# TP-34ren.net
KiCad netlist of a schematic drawn in EAGLE
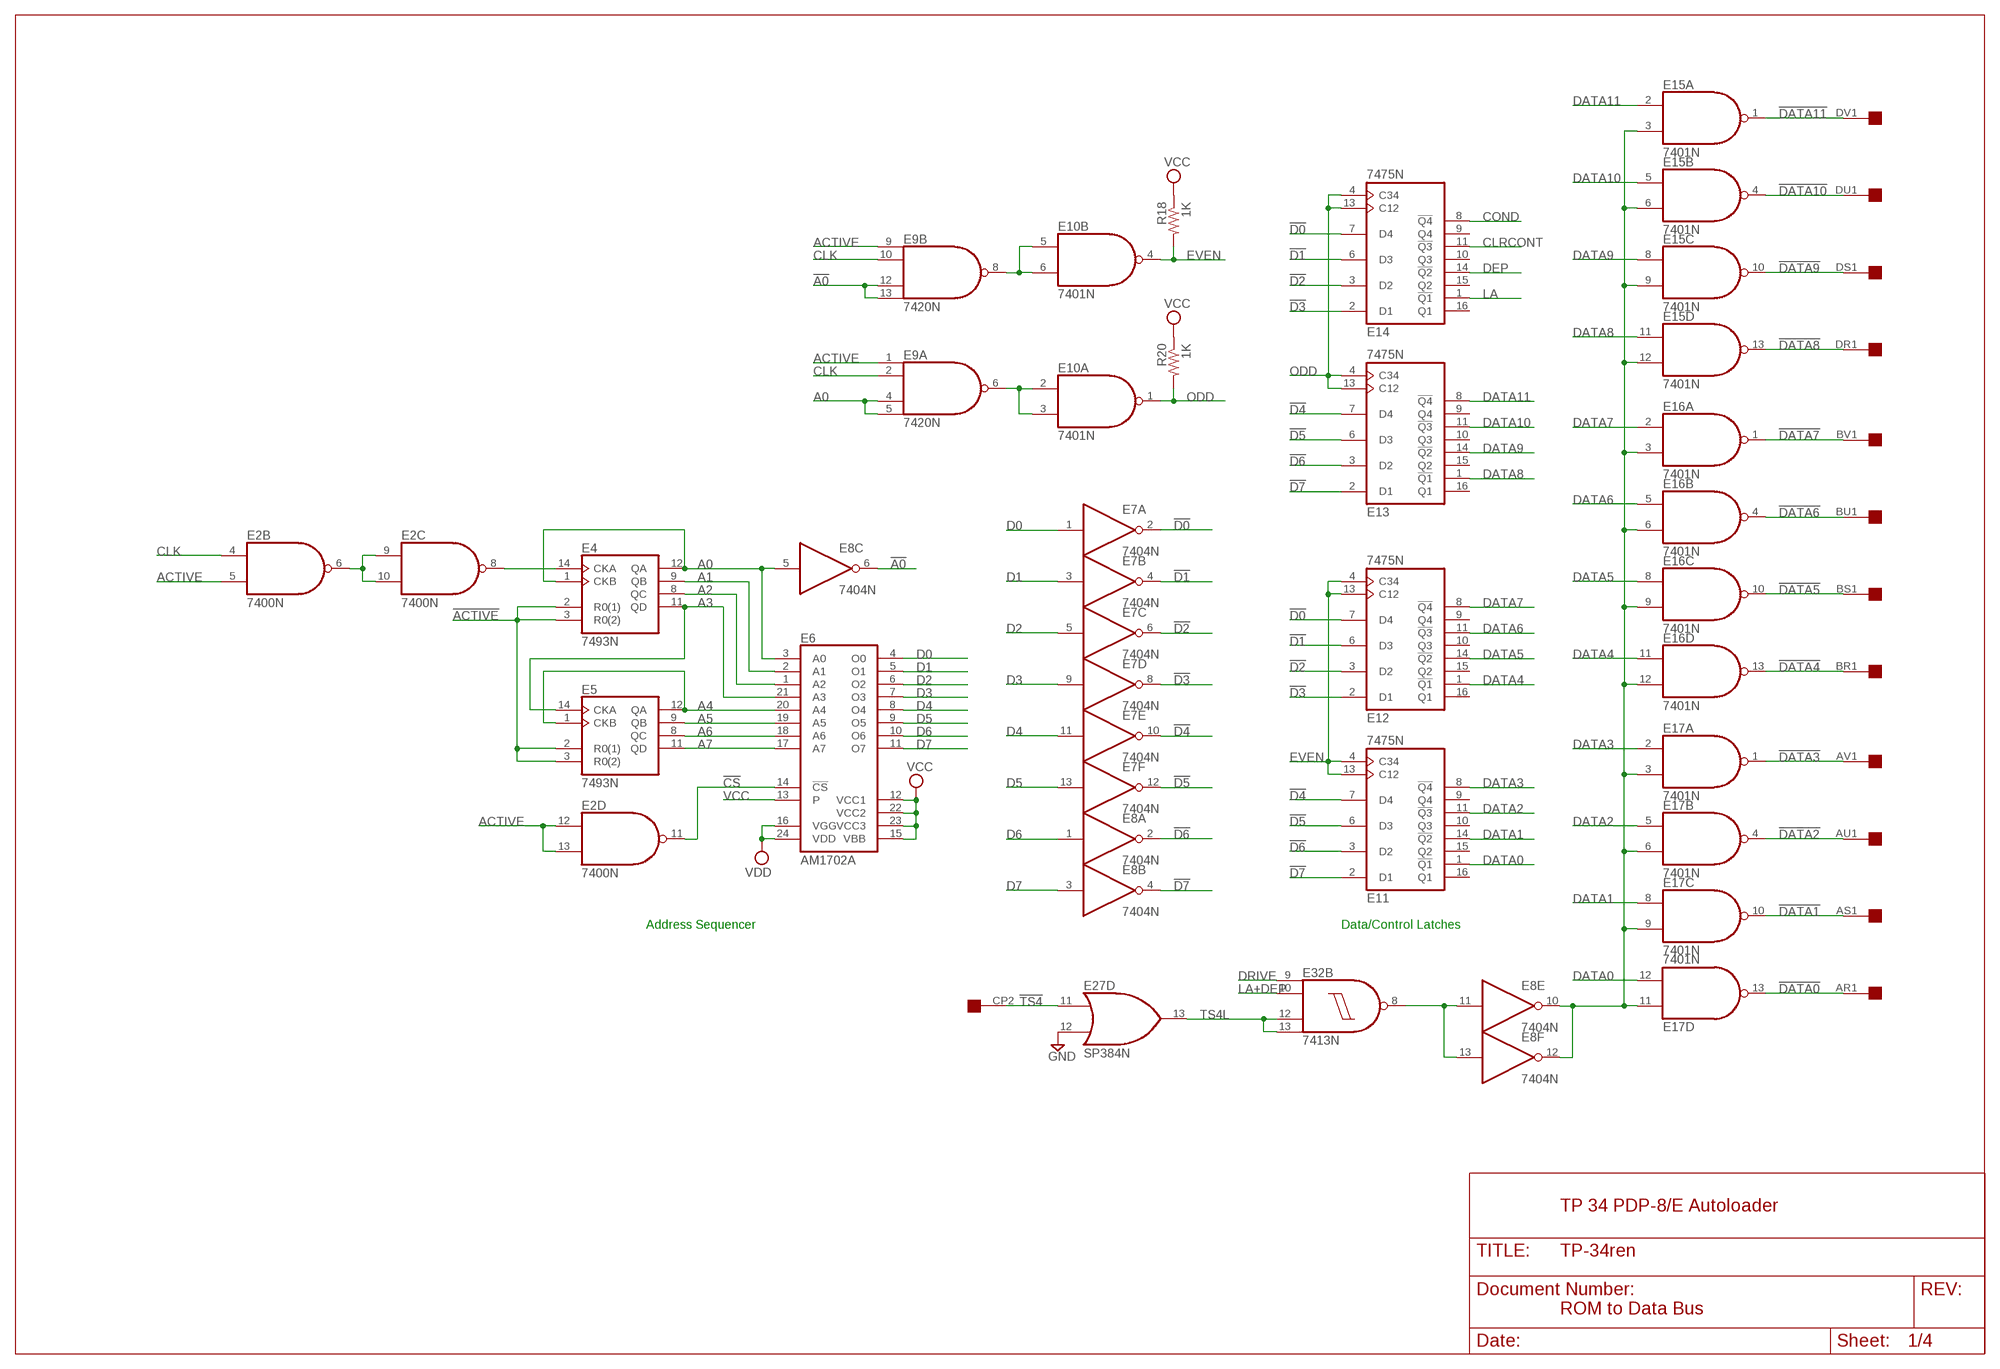
[diagram p0: schematic, sheet 1]
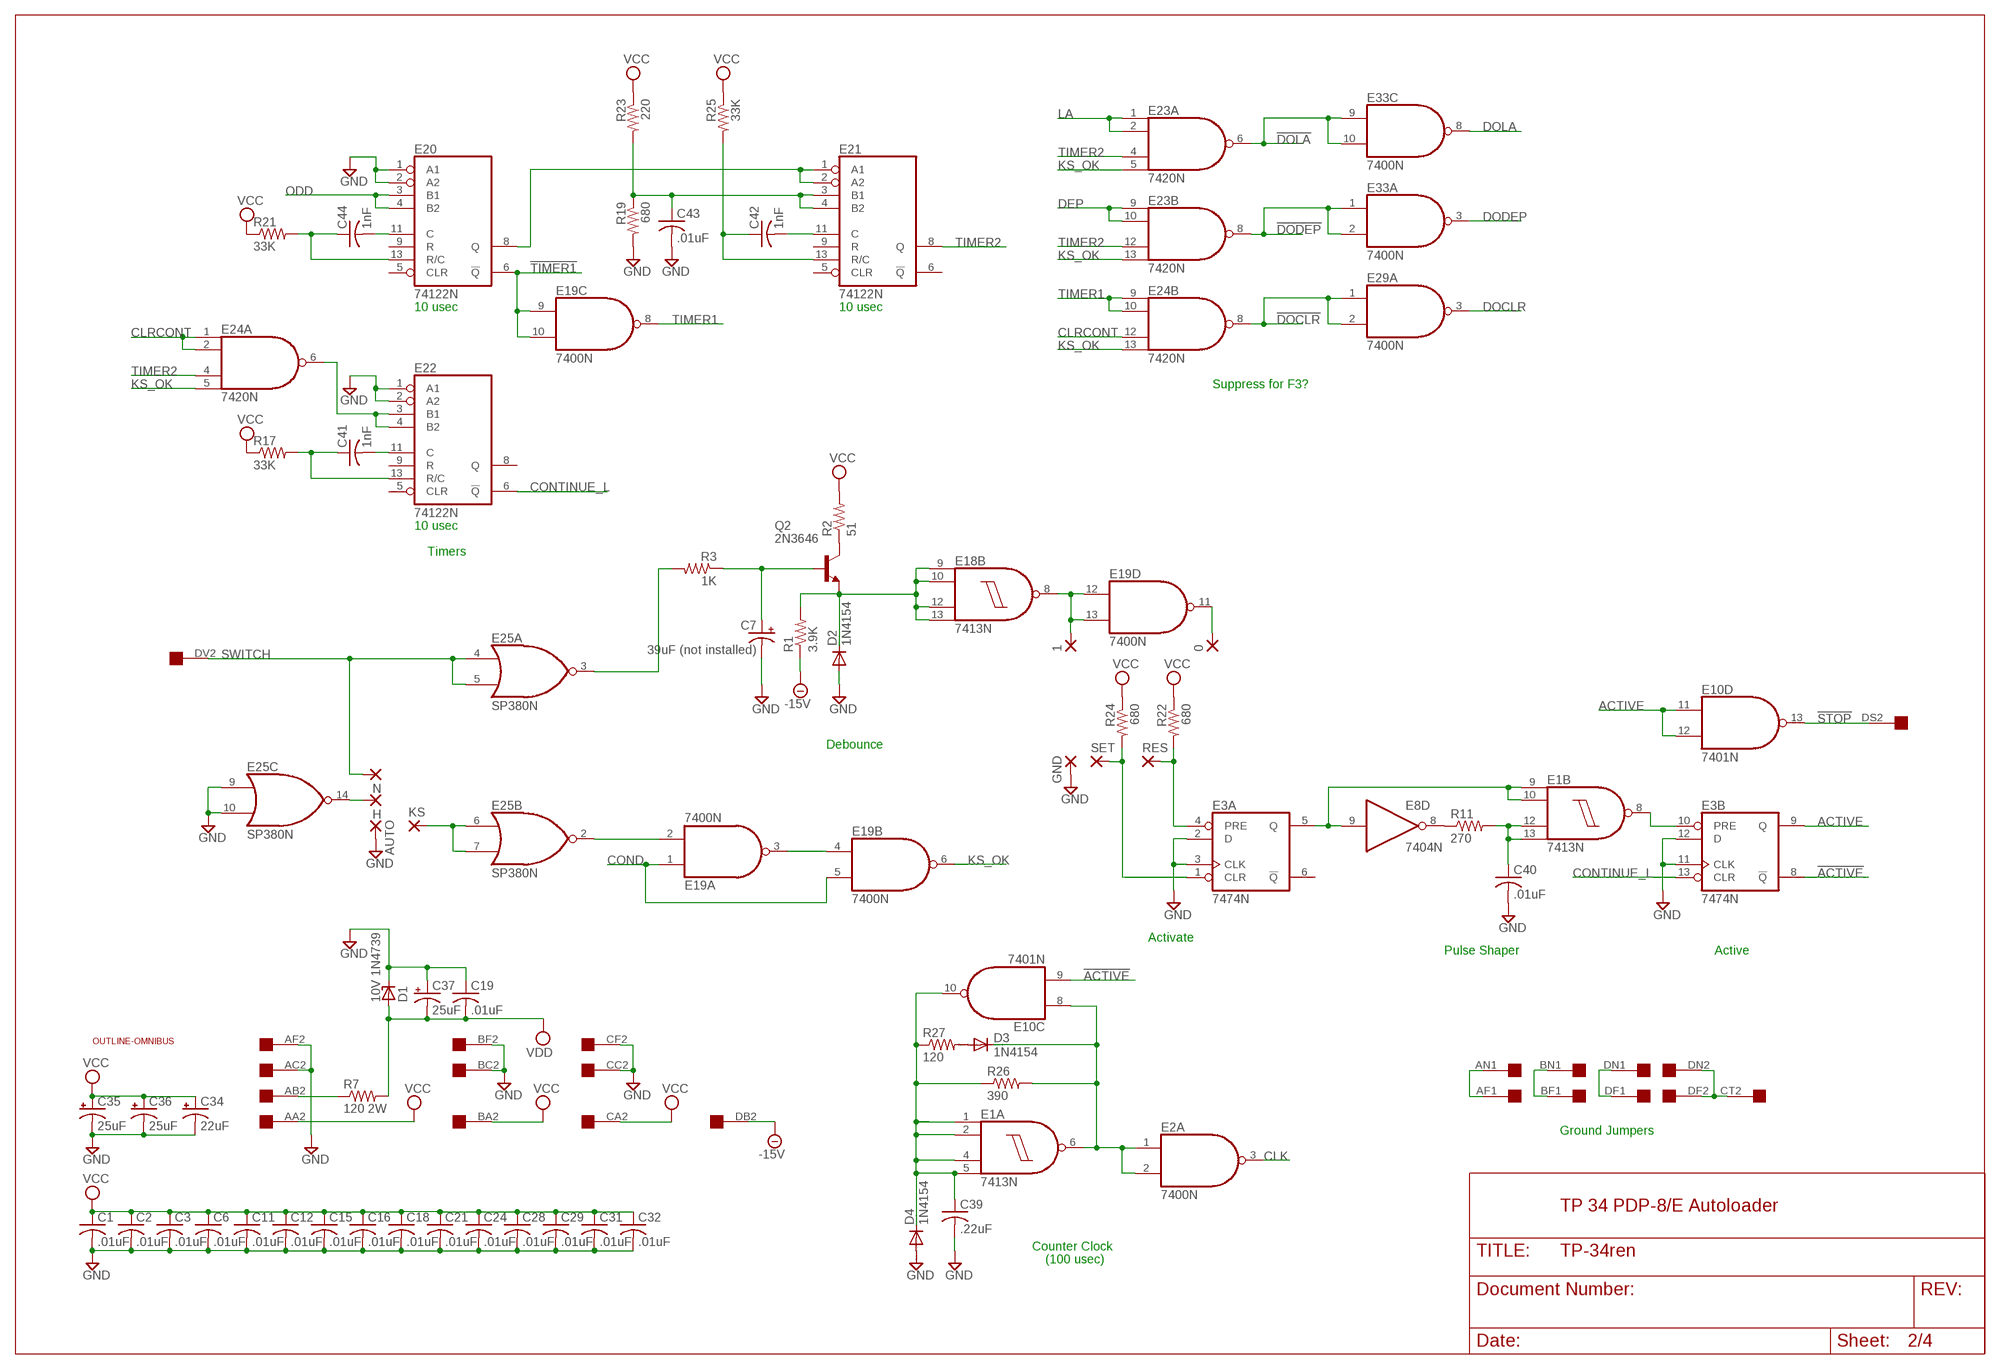
[diagram p1: schematic, sheet 2]
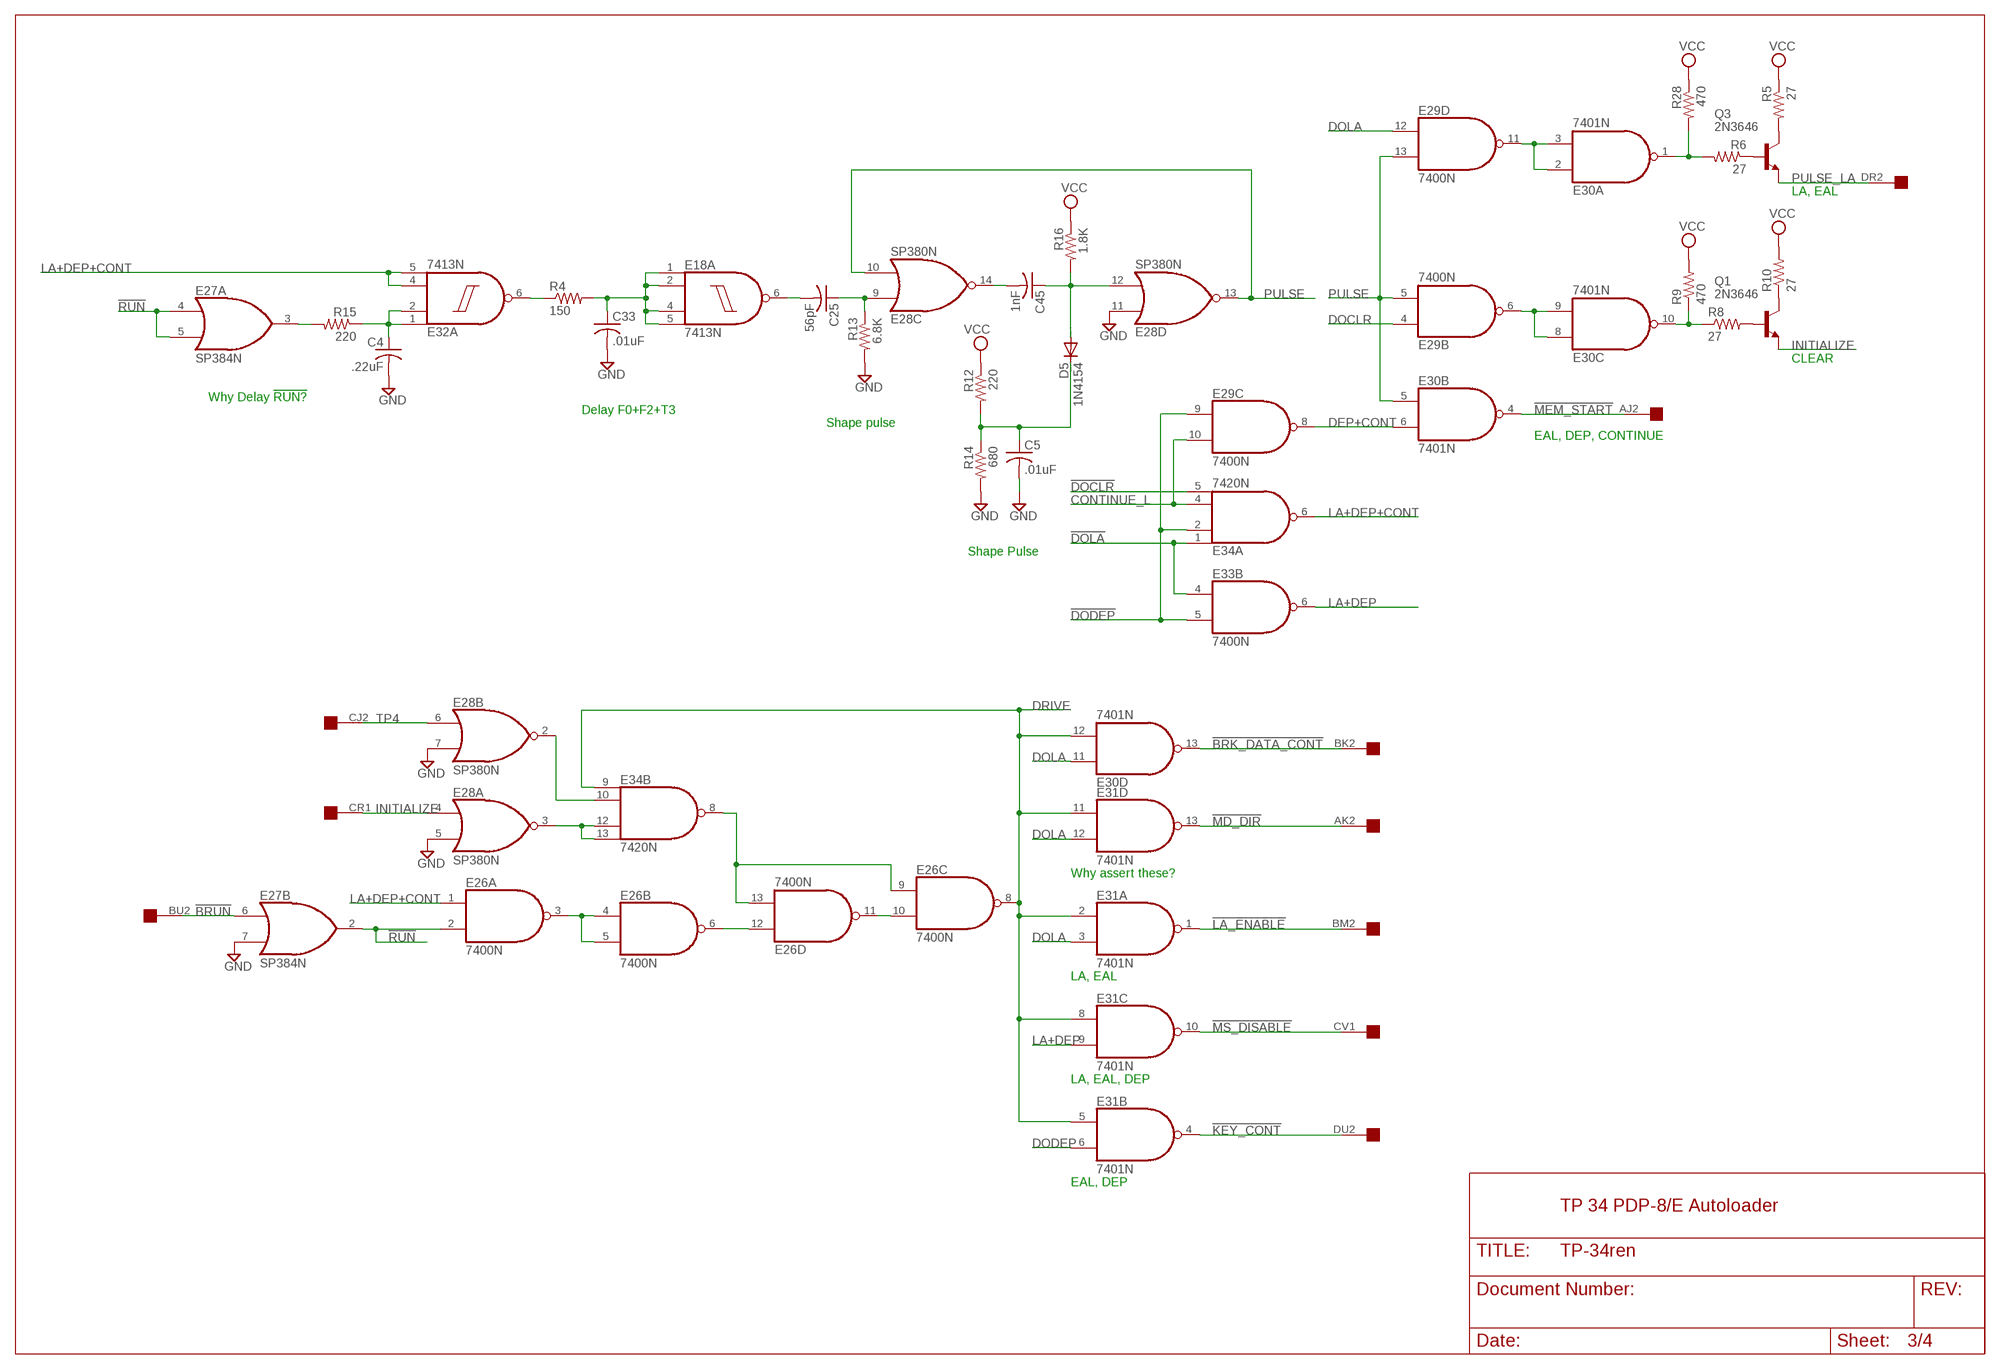
[diagram p2: schematic, sheet 3]
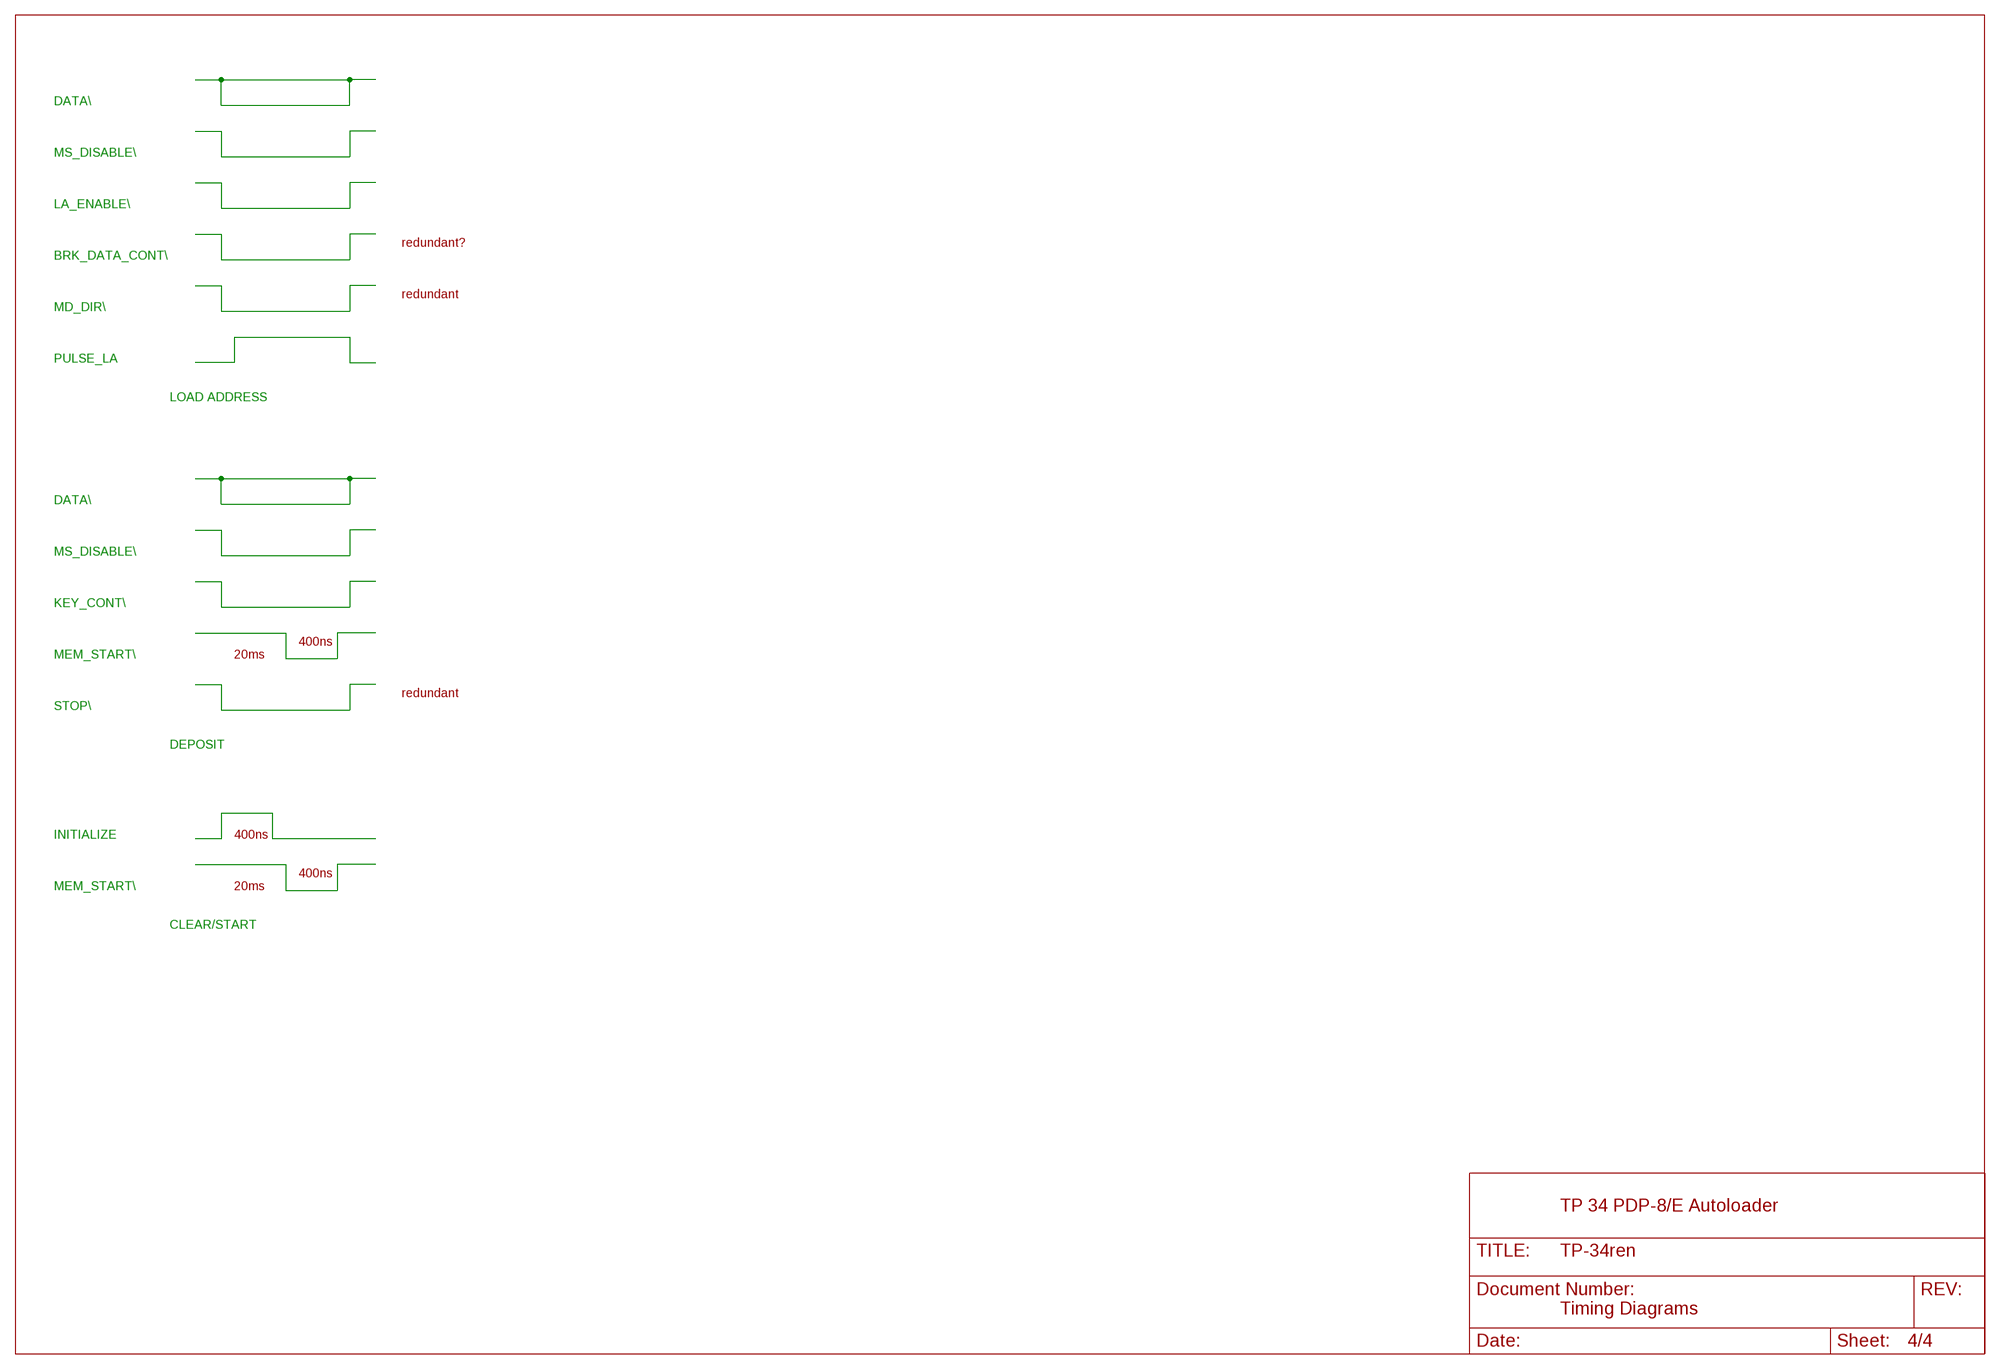
[diagram p3: schematic, sheet 4]

(export (version "E")
  (design (tool "Eeschema 10.0.6"))
  (components
    (comp (ref "0")
      (value "1,6/0,8")
      (footprint "eagle-import:1,6_0,8")
      (libsource (lib "eagle-import") (part "1,6/0,8"))
    )
    (comp (ref "1")
      (value "1,6/0,8")
      (footprint "eagle-import:1,6_0,8")
      (libsource (lib "eagle-import") (part "1,6/0,8"))
    )
    (comp (ref "AUTO")
      (value "1,6/0,8")
      (footprint "eagle-import:1,6_0,8")
      (libsource (lib "eagle-import") (part "1,6/0,8"))
    )
    (comp (ref "C1")
      (value ".01uF")
      (footprint "eagle-import:C075-032X103")
      (libsource (lib "eagle-import") (part "C-US075-032X103"))
    )
    (comp (ref "C2")
      (value ".01uF")
      (footprint "eagle-import:C075-032X103")
      (libsource (lib "eagle-import") (part "C-US075-032X103"))
    )
    (comp (ref "C3")
      (value ".01uF")
      (footprint "eagle-import:C075-032X103")
      (libsource (lib "eagle-import") (part "C-US075-032X103"))
    )
    (comp (ref "C6")
      (value ".01uF")
      (footprint "eagle-import:C075-032X103")
      (libsource (lib "eagle-import") (part "C-US075-032X103"))
    )
    (comp (ref "C7")
      (value "39uF (not installed)")
      (footprint "eagle-import:E15-5")
      (libsource (lib "eagle-import") (part "CPOL-USE15-5AXIAL"))
    )
    (comp (ref "C11")
      (value ".01uF")
      (footprint "eagle-import:C075-032X103")
      (libsource (lib "eagle-import") (part "C-US075-032X103"))
    )
    (comp (ref "C12")
      (value ".01uF")
      (footprint "eagle-import:C075-032X103")
      (libsource (lib "eagle-import") (part "C-US075-032X103"))
    )
    (comp (ref "C15")
      (value ".01uF")
      (footprint "eagle-import:C075-032X103")
      (libsource (lib "eagle-import") (part "C-US075-032X103"))
    )
    (comp (ref "C16")
      (value ".01uF")
      (footprint "eagle-import:C075-032X103")
      (libsource (lib "eagle-import") (part "C-US075-032X103"))
    )
    (comp (ref "C18")
      (value ".01uF")
      (footprint "eagle-import:C075-032X103")
      (libsource (lib "eagle-import") (part "C-US075-032X103"))
    )
    (comp (ref "C19")
      (value ".01uF")
      (footprint "eagle-import:C075-032X103")
      (libsource (lib "eagle-import") (part "C-US075-032X103"))
    )
    (comp (ref "C21")
      (value ".01uF")
      (footprint "eagle-import:C075-032X103")
      (libsource (lib "eagle-import") (part "C-US075-032X103"))
    )
    (comp (ref "C24")
      (value ".01uF")
      (footprint "eagle-import:C075-032X103")
      (libsource (lib "eagle-import") (part "C-US075-032X103"))
    )
    (comp (ref "C28")
      (value ".01uF")
      (footprint "eagle-import:C075-032X103")
      (libsource (lib "eagle-import") (part "C-US075-032X103"))
    )
    (comp (ref "C29")
      (value ".01uF")
      (footprint "eagle-import:C075-032X103")
      (libsource (lib "eagle-import") (part "C-US075-032X103"))
    )
    (comp (ref "C31")
      (value ".01uF")
      (footprint "eagle-import:C075-032X103")
      (libsource (lib "eagle-import") (part "C-US075-032X103"))
    )
    (comp (ref "C32")
      (value ".01uF")
      (footprint "eagle-import:C075-032X103")
      (libsource (lib "eagle-import") (part "C-US075-032X103"))
    )
    (comp (ref "C34")
      (value "22uF")
      (footprint "eagle-import:E12-8")
      (libsource (lib "eagle-import") (part "CPOL-USE20-8AXIAL"))
    )
    (comp (ref "C35")
      (value "25uF")
      (footprint "eagle-import:E15-5")
      (libsource (lib "eagle-import") (part "CPOL-USE15-5AXIAL"))
    )
    (comp (ref "C36")
      (value "25uF")
      (footprint "eagle-import:E15-5")
      (libsource (lib "eagle-import") (part "CPOL-USE15-5AXIAL"))
    )
    (comp (ref "C37")
      (value "25uF")
      (footprint "eagle-import:E15-5")
      (libsource (lib "eagle-import") (part "CPOL-USE15-5AXIAL"))
    )
    (comp (ref "C39")
      (value ".22uF")
      (footprint "eagle-import:C075-032X103")
      (libsource (lib "eagle-import") (part "C-US075-032X103"))
    )
    (comp (ref "C40")
      (value ".01uF")
      (footprint "eagle-import:C075-032X103")
      (libsource (lib "eagle-import") (part "C-US075-032X103"))
    )
    (comp (ref "C41")
      (value "1nF")
      (footprint "eagle-import:C075-032X103")
      (libsource (lib "eagle-import") (part "C-US075-032X103"))
    )
    (comp (ref "C42")
      (value "1nF")
      (footprint "eagle-import:C075-032X103")
      (libsource (lib "eagle-import") (part "C-US075-032X103"))
    )
    (comp (ref "C43")
      (value ".01uF")
      (footprint "eagle-import:C075-032X103")
      (libsource (lib "eagle-import") (part "C-US075-032X103"))
    )
    (comp (ref "C44")
      (value "1nF")
      (footprint "eagle-import:C075-032X103")
      (libsource (lib "eagle-import") (part "C-US075-032X103"))
    )
    (comp (ref "D1")
      (value "10V 1N4739")
      (footprint "eagle-import:C1702-15")
      (libsource (lib "eagle-import") (part "ZENER-DIODEC1702-15"))
    )
    (comp (ref "D2")
      (value "1N4154")
      (footprint "eagle-import:DO35-10")
      (libsource (lib "eagle-import") (part "1N4148DO35-10"))
    )
    (comp (ref "D3")
      (value "1N4154")
      (footprint "eagle-import:DO35-10")
      (libsource (lib "eagle-import") (part "1N4148DO35-10"))
    )
    (comp (ref "D4")
      (value "1N4154")
      (footprint "eagle-import:DO35-10")
      (libsource (lib "eagle-import") (part "1N4148DO35-10"))
    )
    (comp (ref "E1")
      (value "7413N")
      (footprint "eagle-import:DIL14")
      (libsource (lib "eagle-import") (part "7413N"))
    )
    (comp (ref "E2")
      (value "7400N")
      (footprint "eagle-import:DIL14")
      (libsource (lib "eagle-import") (part "7400N"))
    )
    (comp (ref "E3")
      (value "7474N")
      (footprint "eagle-import:DIL14")
      (libsource (lib "eagle-import") (part "7474NS"))
    )
    (comp (ref "E8")
      (value "7404N")
      (footprint "eagle-import:DIL14")
      (libsource (lib "eagle-import") (part "7404N"))
    )
    (comp (ref "E10")
      (value "7401N")
      (footprint "eagle-import:DIL14")
      (libsource (lib "eagle-import") (part "7401NLS"))
    )
    (comp (ref "E18")
      (value "7413N")
      (footprint "eagle-import:DIL14")
      (libsource (lib "eagle-import") (part "7413N"))
    )
    (comp (ref "E19")
      (value "7400N")
      (footprint "eagle-import:DIL14")
      (libsource (lib "eagle-import") (part "7400N"))
    )
    (comp (ref "E20")
      (value "74122N")
      (footprint "eagle-import:DIL14")
      (libsource (lib "eagle-import") (part "74122NLS"))
    )
    (comp (ref "E21")
      (value "74122N")
      (footprint "eagle-import:DIL14")
      (libsource (lib "eagle-import") (part "74122NLS"))
    )
    (comp (ref "E22")
      (value "74122N")
      (footprint "eagle-import:DIL14")
      (libsource (lib "eagle-import") (part "74122NLS"))
    )
    (comp (ref "E23")
      (value "7420N")
      (footprint "eagle-import:DIL14")
      (libsource (lib "eagle-import") (part "7420NS"))
    )
    (comp (ref "E24")
      (value "7420N")
      (footprint "eagle-import:DIL14")
      (libsource (lib "eagle-import") (part "7420NS"))
    )
    (comp (ref "E25")
      (value "SP380N")
      (footprint "eagle-import:DIL14")
      (libsource (lib "eagle-import") (part "SP380N"))
    )
    (comp (ref "E29")
      (value "7400N")
      (footprint "eagle-import:DIL14")
      (libsource (lib "eagle-import") (part "7400N"))
    )
    (comp (ref "E33")
      (value "7400N")
      (footprint "eagle-import:DIL14")
      (libsource (lib "eagle-import") (part "7400N"))
    )
    (comp (ref "GND")
      (value "1,6/0,8")
      (footprint "eagle-import:1,6_0,8")
      (libsource (lib "eagle-import") (part "1,6/0,8"))
    )
    (comp (ref "H")
      (value "1,6/0,8")
      (footprint "eagle-import:1,6_0,8")
      (libsource (lib "eagle-import") (part "1,6/0,8"))
    )
    (comp (ref "KS")
      (value "1,6/0,8")
      (footprint "eagle-import:1,6_0,8")
      (libsource (lib "eagle-import") (part "1,6/0,8"))
    )
    (comp (ref "N")
      (value "1,6/0,8")
      (footprint "eagle-import:1,6_0,8")
      (libsource (lib "eagle-import") (part "1,6/0,8"))
    )
    (comp (ref "Q2")
      (value "2N3646")
      (footprint "eagle-import:TO5")
      (libsource (lib "eagle-import") (part "2N2102"))
    )
    (comp (ref "R1")
      (value "3.9K")
      (footprint "eagle-import:0207_10")
      (libsource (lib "eagle-import") (part "R-US_0207/10"))
    )
    (comp (ref "R2")
      (value "51")
      (footprint "eagle-import:0207_10")
      (libsource (lib "eagle-import") (part "R-US_0207/10"))
    )
    (comp (ref "R3")
      (value "1K")
      (footprint "eagle-import:0207_10")
      (libsource (lib "eagle-import") (part "R-US_0207/10"))
    )
    (comp (ref "R7")
      (value "120 2W")
      (footprint "eagle-import:0414_15")
      (libsource (lib "eagle-import") (part "R-US_0414/15"))
    )
    (comp (ref "R11")
      (value "270")
      (footprint "eagle-import:0207_12")
      (libsource (lib "eagle-import") (part "R-US_0207/12"))
    )
    (comp (ref "R17")
      (value "33K")
      (footprint "eagle-import:0207_10")
      (libsource (lib "eagle-import") (part "R-US_0207/10"))
    )
    (comp (ref "R19")
      (value "680")
      (footprint "eagle-import:0207_10")
      (libsource (lib "eagle-import") (part "R-US_0207/10"))
    )
    (comp (ref "R21")
      (value "33K")
      (footprint "eagle-import:0207_10")
      (libsource (lib "eagle-import") (part "R-US_0207/10"))
    )
    (comp (ref "R22")
      (value "680")
      (footprint "eagle-import:0207_10")
      (libsource (lib "eagle-import") (part "R-US_0207/10"))
    )
    (comp (ref "R23")
      (value "220")
      (footprint "eagle-import:0207_10")
      (libsource (lib "eagle-import") (part "R-US_0207/10"))
    )
    (comp (ref "R24")
      (value "680")
      (footprint "eagle-import:0207_10")
      (libsource (lib "eagle-import") (part "R-US_0207/10"))
    )
    (comp (ref "R25")
      (value "33K")
      (footprint "eagle-import:0207_10")
      (libsource (lib "eagle-import") (part "R-US_0207/10"))
    )
    (comp (ref "R26")
      (value "390")
      (footprint "eagle-import:0207_10")
      (libsource (lib "eagle-import") (part "R-US_0207/10"))
    )
    (comp (ref "R27")
      (value "120")
      (footprint "eagle-import:0207_10")
      (libsource (lib "eagle-import") (part "R-US_0207/10"))
    )
    (comp (ref "RES")
      (value "1,6/0,8")
      (footprint "eagle-import:1,6_0,8")
      (libsource (lib "eagle-import") (part "1,6/0,8"))
    )
    (comp (ref "SET")
      (value "1,6/0,8")
      (footprint "eagle-import:1,6_0,8")
      (libsource (lib "eagle-import") (part "1,6/0,8"))
    )
    (comp (ref "U$1")
      (value "OUTLINE-OMNIBUS")
      (footprint "eagle-import:OMNIBUS")
      (libsource (lib "eagle-import") (part "OUTLINE-OMNIBUS"))
    )
    (comp (ref "U$2")
      (value "QUAD")
      (footprint "eagle-import:EDGE-CON8")
      (libsource (lib "eagle-import") (part "QUAD"))
    )
    (comp (ref "E4")
      (value "7493N")
      (footprint "eagle-import:DIL14")
      (libsource (lib "eagle-import") (part "7493NLS"))
    )
    (comp (ref "E5")
      (value "7493N")
      (footprint "eagle-import:DIL14")
      (libsource (lib "eagle-import") (part "7493NLS"))
    )
    (comp (ref "E6")
      (value "AM1702A")
      (footprint "eagle-import:DIL24")
      (libsource (lib "eagle-import") (part "AM1702"))
    )
    (comp (ref "E7")
      (value "7404N")
      (footprint "eagle-import:DIL14")
      (libsource (lib "eagle-import") (part "7404N"))
    )
    (comp (ref "E9")
      (value "7420N")
      (footprint "eagle-import:DIL14")
      (libsource (lib "eagle-import") (part "7420NS"))
    )
    (comp (ref "E11")
      (value "7475N")
      (footprint "eagle-import:DIL16")
      (libsource (lib "eagle-import") (part "7475N"))
    )
    (comp (ref "E12")
      (value "7475N")
      (footprint "eagle-import:DIL16")
      (libsource (lib "eagle-import") (part "7475N"))
    )
    (comp (ref "E13")
      (value "7475N")
      (footprint "eagle-import:DIL16")
      (libsource (lib "eagle-import") (part "7475N"))
    )
    (comp (ref "E14")
      (value "7475N")
      (footprint "eagle-import:DIL16")
      (libsource (lib "eagle-import") (part "7475N"))
    )
    (comp (ref "E15")
      (value "7401N")
      (footprint "eagle-import:DIL14")
      (libsource (lib "eagle-import") (part "7401NLS"))
    )
    (comp (ref "E16")
      (value "7401N")
      (footprint "eagle-import:DIL14")
      (libsource (lib "eagle-import") (part "7401NLS"))
    )
    (comp (ref "E17")
      (value "7401N")
      (footprint "eagle-import:DIL14")
      (libsource (lib "eagle-import") (part "7401NLS"))
    )
    (comp (ref "E27")
      (value "SP384N")
      (footprint "eagle-import:DIL14")
      (libsource (lib "eagle-import") (part "SP384N"))
    )
    (comp (ref "E32")
      (value "7413N")
      (footprint "eagle-import:DIL14")
      (libsource (lib "eagle-import") (part "7413N"))
    )
    (comp (ref "R18")
      (value "1K")
      (footprint "eagle-import:0207_10")
      (libsource (lib "eagle-import") (part "R-US_0207/10"))
    )
    (comp (ref "R20")
      (value "1K")
      (footprint "eagle-import:0207_10")
      (libsource (lib "eagle-import") (part "R-US_0207/10"))
    )
    (comp (ref "C4")
      (value ".22uF")
      (footprint "eagle-import:C075-032X103")
      (libsource (lib "eagle-import") (part "C-US075-032X103"))
    )
    (comp (ref "C5")
      (value ".01uF")
      (footprint "eagle-import:C075-032X103")
      (libsource (lib "eagle-import") (part "C-US075-032X103"))
    )
    (comp (ref "C25")
      (value "56pF")
      (footprint "eagle-import:C102-043X133")
      (libsource (lib "eagle-import") (part "C-US102-043X133"))
    )
    (comp (ref "C33")
      (value ".01uF")
      (footprint "eagle-import:C075-032X103")
      (libsource (lib "eagle-import") (part "C-US075-032X103"))
    )
    (comp (ref "C45")
      (value "1nF")
      (footprint "eagle-import:C050-035X075")
      (libsource (lib "eagle-import") (part "C-US050-035X075"))
    )
    (comp (ref "D5")
      (value "1N4154")
      (footprint "eagle-import:DO35-10")
      (libsource (lib "eagle-import") (part "1N4148DO35-10"))
    )
    (comp (ref "E26")
      (value "7400N")
      (footprint "eagle-import:DIL14")
      (libsource (lib "eagle-import") (part "7400N"))
    )
    (comp (ref "E28")
      (value "SP380N")
      (footprint "eagle-import:DIL14")
      (libsource (lib "eagle-import") (part "SP380N"))
    )
    (comp (ref "E30")
      (value "7401N")
      (footprint "eagle-import:DIL14")
      (libsource (lib "eagle-import") (part "7401NLS"))
    )
    (comp (ref "E31")
      (value "7401N")
      (footprint "eagle-import:DIL14")
      (libsource (lib "eagle-import") (part "7401NLS"))
    )
    (comp (ref "E34")
      (value "7420N")
      (footprint "eagle-import:DIL14")
      (libsource (lib "eagle-import") (part "7420NS"))
    )
    (comp (ref "Q1")
      (value "2N3646")
      (footprint "eagle-import:TO5")
      (libsource (lib "eagle-import") (part "2N2102"))
    )
    (comp (ref "Q3")
      (value "2N3646")
      (footprint "eagle-import:TO5")
      (libsource (lib "eagle-import") (part "2N2102"))
    )
    (comp (ref "R4")
      (value "150")
      (footprint "eagle-import:0207_10")
      (libsource (lib "eagle-import") (part "R-US_0207/10"))
    )
    (comp (ref "R5")
      (value "27")
      (footprint "eagle-import:0207_10")
      (libsource (lib "eagle-import") (part "R-US_0207/10"))
    )
    (comp (ref "R6")
      (value "27")
      (footprint "eagle-import:0207_10")
      (libsource (lib "eagle-import") (part "R-US_0207/10"))
    )
    (comp (ref "R8")
      (value "27")
      (footprint "eagle-import:0207_10")
      (libsource (lib "eagle-import") (part "R-US_0207/10"))
    )
    (comp (ref "R9")
      (value "470")
      (footprint "eagle-import:0207_10")
      (libsource (lib "eagle-import") (part "R-US_0207/10"))
    )
    (comp (ref "R10")
      (value "27")
      (footprint "eagle-import:0207_10")
      (libsource (lib "eagle-import") (part "R-US_0207/10"))
    )
    (comp (ref "R12")
      (value "220")
      (footprint "eagle-import:0207_10")
      (libsource (lib "eagle-import") (part "R-US_0207/10"))
    )
    (comp (ref "R13")
      (value "6.8K")
      (footprint "eagle-import:0207_10")
      (libsource (lib "eagle-import") (part "R-US_0207/10"))
    )
    (comp (ref "R14")
      (value "680")
      (footprint "eagle-import:0207_10")
      (libsource (lib "eagle-import") (part "R-US_0207/10"))
    )
    (comp (ref "R15")
      (value "220")
      (footprint "eagle-import:0207_15")
      (libsource (lib "eagle-import") (part "R-US_0207/15"))
    )
    (comp (ref "R16")
      (value "1.8K")
      (footprint "eagle-import:0207_10")
      (libsource (lib "eagle-import") (part "R-US_0207/10"))
    )
    (comp (ref "R28")
      (value "470")
      (footprint "eagle-import:0207_10")
      (libsource (lib "eagle-import") (part "R-US_0207/10"))
    )
  )
  (nets
    (net (code "1") (name "-15V") (class "Default")
      (node (ref "R1") (pin "1") (pinfunction "1_1") (pintype "passive"))
      (node (ref "U$2") (pin "DB2") (pinfunction "1_DB2") (pintype "bidirectional"))
    )
    (net (code "2") (name "A0") (class "Default")
      (node (ref "E4") (pin "1") (pinfunction "CKB_1") (pintype "input"))
      (node (ref "E4") (pin "12") (pinfunction "QA_12") (pintype "output"))
      (node (ref "E6") (pin "3") (pinfunction "A0_3") (pintype "input"))
      (node (ref "E8") (pin "5") (pinfunction "I_5") (pintype "input"))
      (node (ref "E9") (pin "4") (pinfunction "I2_4") (pintype "input"))
      (node (ref "E9") (pin "5") (pinfunction "I3_5") (pintype "input"))
    )
    (net (code "3") (name "A1") (class "Default")
      (node (ref "E4") (pin "9") (pinfunction "QB_9") (pintype "output"))
      (node (ref "E6") (pin "2") (pinfunction "A1_2") (pintype "input"))
    )
    (net (code "4") (name "A2") (class "Default")
      (node (ref "E4") (pin "8") (pinfunction "QC_8") (pintype "output"))
      (node (ref "E6") (pin "1") (pinfunction "A2_1") (pintype "input"))
    )
    (net (code "5") (name "A3") (class "Default")
      (node (ref "E4") (pin "11") (pinfunction "QD_11") (pintype "output"))
      (node (ref "E5") (pin "14") (pinfunction "CKA_14") (pintype "input"))
      (node (ref "E6") (pin "21") (pinfunction "A3_21") (pintype "input"))
    )
    (net (code "6") (name "A4") (class "Default")
      (node (ref "E5") (pin "1") (pinfunction "CKB_1") (pintype "input"))
      (node (ref "E5") (pin "12") (pinfunction "QA_12") (pintype "output"))
      (node (ref "E6") (pin "20") (pinfunction "A4_20") (pintype "input"))
    )
    (net (code "7") (name "A5") (class "Default")
      (node (ref "E5") (pin "9") (pinfunction "QB_9") (pintype "output"))
      (node (ref "E6") (pin "19") (pinfunction "A5_19") (pintype "input"))
    )
    (net (code "8") (name "A6") (class "Default")
      (node (ref "E5") (pin "8") (pinfunction "QC_8") (pintype "output"))
      (node (ref "E6") (pin "18") (pinfunction "A6_18") (pintype "input"))
    )
    (net (code "9") (name "A7") (class "Default")
      (node (ref "E5") (pin "11") (pinfunction "QD_11") (pintype "output"))
      (node (ref "E6") (pin "17") (pinfunction "A7_17") (pintype "input"))
    )
    (net (code "10") (name "ACTIVE") (class "Default")
      (node (ref "E10") (pin "11") (pinfunction "I0_11") (pintype "input"))
      (node (ref "E10") (pin "12") (pinfunction "I1_12") (pintype "input"))
      (node (ref "E2") (pin "12") (pinfunction "I0_12") (pintype "input"))
      (node (ref "E2") (pin "13") (pinfunction "I1_13") (pintype "input"))
      (node (ref "E2") (pin "5") (pinfunction "I1_5") (pintype "input"))
      (node (ref "E3") (pin "9") (pinfunction "Q_9") (pintype "output"))
      (node (ref "E9") (pin "1") (pinfunction "I0_1") (pintype "input"))
      (node (ref "E9") (pin "9") (pinfunction "I0_9") (pintype "input"))
    )
    (net (code "11") (name "CLK") (class "Default")
      (node (ref "E2") (pin "3") (pinfunction "O_3") (pintype "output"))
      (node (ref "E2") (pin "4") (pinfunction "I0_4") (pintype "input"))
      (node (ref "E9") (pin "10") (pinfunction "I1_10") (pintype "input"))
      (node (ref "E9") (pin "2") (pinfunction "I1_2") (pintype "input"))
    )
    (net (code "12") (name "CLRCONT") (class "Default")
      (node (ref "E14") (pin "11") (pinfunction "~{Q3}_11") (pintype "output"))
      (node (ref "E24") (pin "1") (pinfunction "I0_1") (pintype "input"))
      (node (ref "E24") (pin "12") (pinfunction "I2_12") (pintype "input"))
      (node (ref "E24") (pin "2") (pinfunction "I1_2") (pintype "input"))
    )
    (net (code "13") (name "COND") (class "Default")
      (node (ref "E14") (pin "8") (pinfunction "~{Q4}_8") (pintype "output"))
      (node (ref "E19") (pin "1") (pinfunction "I0_1") (pintype "input"))
      (node (ref "E19") (pin "5") (pinfunction "I1_5") (pintype "input"))
    )
    (net (code "14") (name "CONTINUE_L") (class "Default")
      (node (ref "E22") (pin "6") (pinfunction "~{Q}_6") (pintype "output"))
      (node (ref "E29") (pin "10") (pinfunction "I1_10") (pintype "input"))
      (node (ref "E3") (pin "13") (pinfunction "CLR_13") (pintype "input"))
      (node (ref "E34") (pin "4") (pinfunction "I2_4") (pintype "input"))
    )
    (net (code "15") (name "D0") (class "Default")
      (node (ref "E6") (pin "4") (pinfunction "O0_4") (pintype "tri_state"))
      (node (ref "E7") (pin "1") (pinfunction "I_1") (pintype "input"))
    )
    (net (code "16") (name "D1") (class "Default")
      (node (ref "E6") (pin "5") (pinfunction "O1_5") (pintype "tri_state"))
      (node (ref "E7") (pin "3") (pinfunction "I_3") (pintype "input"))
    )
    (net (code "17") (name "D2") (class "Default")
      (node (ref "E6") (pin "6") (pinfunction "O2_6") (pintype "tri_state"))
      (node (ref "E7") (pin "5") (pinfunction "I_5") (pintype "input"))
    )
    (net (code "18") (name "D3") (class "Default")
      (node (ref "E6") (pin "7") (pinfunction "O3_7") (pintype "tri_state"))
      (node (ref "E7") (pin "9") (pinfunction "I_9") (pintype "input"))
    )
    (net (code "19") (name "D4") (class "Default")
      (node (ref "E6") (pin "8") (pinfunction "O4_8") (pintype "tri_state"))
      (node (ref "E7") (pin "11") (pinfunction "I_11") (pintype "input"))
    )
    (net (code "20") (name "D5") (class "Default")
      (node (ref "E6") (pin "9") (pinfunction "O5_9") (pintype "tri_state"))
      (node (ref "E7") (pin "13") (pinfunction "I_13") (pintype "input"))
    )
    (net (code "21") (name "D6") (class "Default")
      (node (ref "E6") (pin "10") (pinfunction "O6_10") (pintype "tri_state"))
      (node (ref "E8") (pin "1") (pinfunction "I_1") (pintype "input"))
    )
    (net (code "22") (name "D7") (class "Default")
      (node (ref "E6") (pin "11") (pinfunction "O7_11") (pintype "tri_state"))
      (node (ref "E8") (pin "3") (pinfunction "I_3") (pintype "input"))
    )
    (net (code "23") (name "DATA0") (class "Default")
      (node (ref "E11") (pin "1") (pinfunction "~{Q1}_1") (pintype "output"))
      (node (ref "E17") (pin "12") (pinfunction "I1_12") (pintype "input"))
    )
    (net (code "24") (name "DATA1") (class "Default")
      (node (ref "E11") (pin "14") (pinfunction "~{Q2}_14") (pintype "output"))
      (node (ref "E17") (pin "8") (pinfunction "I0_8") (pintype "input"))
    )
    (net (code "25") (name "DATA2") (class "Default")
      (node (ref "E11") (pin "11") (pinfunction "~{Q3}_11") (pintype "output"))
      (node (ref "E17") (pin "5") (pinfunction "I0_5") (pintype "input"))
    )
    (net (code "26") (name "DATA3") (class "Default")
      (node (ref "E11") (pin "8") (pinfunction "~{Q4}_8") (pintype "output"))
      (node (ref "E17") (pin "2") (pinfunction "I0_2") (pintype "input"))
    )
    (net (code "27") (name "DATA4") (class "Default")
      (node (ref "E12") (pin "1") (pinfunction "~{Q1}_1") (pintype "output"))
      (node (ref "E16") (pin "11") (pinfunction "I0_11") (pintype "input"))
    )
    (net (code "28") (name "DATA5") (class "Default")
      (node (ref "E12") (pin "14") (pinfunction "~{Q2}_14") (pintype "output"))
      (node (ref "E16") (pin "8") (pinfunction "I0_8") (pintype "input"))
    )
    (net (code "29") (name "DATA6") (class "Default")
      (node (ref "E12") (pin "11") (pinfunction "~{Q3}_11") (pintype "output"))
      (node (ref "E16") (pin "5") (pinfunction "I0_5") (pintype "input"))
    )
    (net (code "30") (name "DATA7") (class "Default")
      (node (ref "E12") (pin "8") (pinfunction "~{Q4}_8") (pintype "output"))
      (node (ref "E16") (pin "2") (pinfunction "I0_2") (pintype "input"))
    )
    (net (code "31") (name "DATA8") (class "Default")
      (node (ref "E13") (pin "1") (pinfunction "~{Q1}_1") (pintype "output"))
      (node (ref "E15") (pin "11") (pinfunction "I0_11") (pintype "input"))
    )
    (net (code "32") (name "DATA9") (class "Default")
      (node (ref "E13") (pin "14") (pinfunction "~{Q2}_14") (pintype "output"))
      (node (ref "E15") (pin "8") (pinfunction "I0_8") (pintype "input"))
    )
    (net (code "33") (name "DATA10") (class "Default")
      (node (ref "E13") (pin "11") (pinfunction "~{Q3}_11") (pintype "output"))
      (node (ref "E15") (pin "5") (pinfunction "I0_5") (pintype "input"))
    )
    (net (code "34") (name "DATA11") (class "Default")
      (node (ref "E13") (pin "8") (pinfunction "~{Q4}_8") (pintype "output"))
      (node (ref "E15") (pin "2") (pinfunction "I0_2") (pintype "input"))
    )
    (net (code "35") (name "DEP") (class "Default")
      (node (ref "E14") (pin "14") (pinfunction "~{Q2}_14") (pintype "output"))
      (node (ref "E23") (pin "10") (pinfunction "I1_10") (pintype "input"))
      (node (ref "E23") (pin "9") (pinfunction "I0_9") (pintype "input"))
    )
    (net (code "36") (name "DEP+CONT") (class "Default")
      (node (ref "E29") (pin "8") (pinfunction "O_8") (pintype "output"))
      (node (ref "E30") (pin "6") (pinfunction "I1_6") (pintype "input"))
    )
    (net (code "37") (name "DOCLR") (class "Default")
      (node (ref "E29") (pin "3") (pinfunction "O_3") (pintype "output"))
      (node (ref "E29") (pin "4") (pinfunction "I0_4") (pintype "input"))
    )
    (net (code "38") (name "DODEP") (class "Default")
      (node (ref "E31") (pin "6") (pinfunction "I1_6") (pintype "input"))
      (node (ref "E33") (pin "3") (pinfunction "O_3") (pintype "output"))
    )
    (net (code "39") (name "DOLA") (class "Default")
      (node (ref "E29") (pin "12") (pinfunction "I0_12") (pintype "input"))
      (node (ref "E30") (pin "11") (pinfunction "I0_11") (pintype "input"))
      (node (ref "E31") (pin "12") (pinfunction "I1_12") (pintype "input"))
      (node (ref "E31") (pin "3") (pinfunction "I1_3") (pintype "input"))
      (node (ref "E33") (pin "8") (pinfunction "O_8") (pintype "output"))
    )
    (net (code "40") (name "DRIVE") (class "Default")
      (node (ref "E26") (pin "8") (pinfunction "O_8") (pintype "output"))
      (node (ref "E30") (pin "12") (pinfunction "I1_12") (pintype "input"))
      (node (ref "E31") (pin "11") (pinfunction "I0_11") (pintype "input"))
      (node (ref "E31") (pin "2") (pinfunction "I0_2") (pintype "input"))
      (node (ref "E31") (pin "5") (pinfunction "I0_5") (pintype "input"))
      (node (ref "E31") (pin "8") (pinfunction "I0_8") (pintype "input"))
      (node (ref "E32") (pin "9") (pinfunction "I0_9") (pintype "input"))
      (node (ref "E34") (pin "9") (pinfunction "I0_9") (pintype "input"))
    )
    (net (code "41") (name "EVEN") (class "Default")
      (node (ref "E10") (pin "4") (pinfunction "O_4") (pintype "open_collector"))
      (node (ref "E11") (pin "13") (pinfunction "C12_13") (pintype "input"))
      (node (ref "E11") (pin "4") (pinfunction "C34_4") (pintype "input"))
      (node (ref "E12") (pin "13") (pinfunction "C12_13") (pintype "input"))
      (node (ref "E12") (pin "4") (pinfunction "C34_4") (pintype "input"))
      (node (ref "R18") (pin "2") (pinfunction "2_2") (pintype "passive"))
    )
    (net (code "42") (name "GND") (class "Default")
      (node (ref "AUTO") (pin "1") (pinfunction "P_1") (pintype "passive"))
      (node (ref "C1") (pin "2") (pinfunction "2_2") (pintype "passive"))
      (node (ref "C11") (pin "2") (pinfunction "2_2") (pintype "passive"))
      (node (ref "C12") (pin "2") (pinfunction "2_2") (pintype "passive"))
      (node (ref "C15") (pin "2") (pinfunction "2_2") (pintype "passive"))
      (node (ref "C16") (pin "2") (pinfunction "2_2") (pintype "passive"))
      (node (ref "C18") (pin "2") (pinfunction "2_2") (pintype "passive"))
      (node (ref "C19") (pin "1") (pinfunction "1_1") (pintype "passive"))
      (node (ref "C2") (pin "2") (pinfunction "2_2") (pintype "passive"))
      (node (ref "C21") (pin "2") (pinfunction "2_2") (pintype "passive"))
      (node (ref "C24") (pin "2") (pinfunction "2_2") (pintype "passive"))
      (node (ref "C28") (pin "2") (pinfunction "2_2") (pintype "passive"))
      (node (ref "C29") (pin "2") (pinfunction "2_2") (pintype "passive"))
      (node (ref "C3") (pin "2") (pinfunction "2_2") (pintype "passive"))
      (node (ref "C31") (pin "2") (pinfunction "2_2") (pintype "passive"))
      (node (ref "C32") (pin "2") (pinfunction "2_2") (pintype "passive"))
      (node (ref "C33") (pin "2") (pinfunction "2_2") (pintype "passive"))
      (node (ref "C34") (pin "-") (pinfunction "-_-") (pintype "passive"))
      (node (ref "C35") (pin "-") (pinfunction "-_-") (pintype "passive"))
      (node (ref "C36") (pin "-") (pinfunction "-_-") (pintype "passive"))
      (node (ref "C37") (pin "+") (pinfunction "+_+") (pintype "passive"))
      (node (ref "C39") (pin "2") (pinfunction "2_2") (pintype "passive"))
      (node (ref "C4") (pin "2") (pinfunction "2_2") (pintype "passive"))
      (node (ref "C40") (pin "2") (pinfunction "2_2") (pintype "passive"))
      (node (ref "C43") (pin "2") (pinfunction "2_2") (pintype "passive"))
      (node (ref "C5") (pin "2") (pinfunction "2_2") (pintype "passive"))
      (node (ref "C6") (pin "2") (pinfunction "2_2") (pintype "passive"))
      (node (ref "C7") (pin "-") (pinfunction "-_-") (pintype "passive"))
      (node (ref "D1") (pin "C") (pinfunction "C_C") (pintype "passive"))
      (node (ref "D2") (pin "A") (pinfunction "A_A") (pintype "passive"))
      (node (ref "D4") (pin "A") (pinfunction "A_A") (pintype "passive"))
      (node (ref "E20") (pin "1") (pinfunction "A1_1") (pintype "input"))
      (node (ref "E20") (pin "2") (pinfunction "A2_2") (pintype "input"))
      (node (ref "E22") (pin "1") (pinfunction "A1_1") (pintype "input"))
      (node (ref "E22") (pin "2") (pinfunction "A2_2") (pintype "input"))
      (node (ref "E25") (pin "10") (pinfunction "I1_10") (pintype "input"))
      (node (ref "E25") (pin "9") (pinfunction "I0_9") (pintype "input"))
      (node (ref "E27") (pin "12") (pinfunction "I1_12") (pintype "input"))
      (node (ref "E27") (pin "7") (pinfunction "I1_7") (pintype "input"))
      (node (ref "E28") (pin "11") (pinfunction "I0_11") (pintype "input"))
      (node (ref "E28") (pin "5") (pinfunction "I1_5") (pintype "input"))
      (node (ref "E28") (pin "7") (pinfunction "I1_7") (pintype "input"))
      (node (ref "E3") (pin "11") (pinfunction "CLK_11") (pintype "input"))
      (node (ref "E3") (pin "12") (pinfunction "D_12") (pintype "input"))
      (node (ref "E3") (pin "2") (pinfunction "D_2") (pintype "input"))
      (node (ref "E3") (pin "3") (pinfunction "CLK_3") (pintype "input"))
      (node (ref "GND") (pin "1") (pinfunction "P_1") (pintype "passive"))
      (node (ref "R13") (pin "2") (pinfunction "2_2") (pintype "passive"))
      (node (ref "R14") (pin "2") (pinfunction "2_2") (pintype "passive"))
      (node (ref "R19") (pin "2") (pinfunction "2_2") (pintype "passive"))
      (node (ref "U$2") (pin "AC2") (pinfunction "1_AC2") (pintype "bidirectional"))
      (node (ref "U$2") (pin "AF2") (pinfunction "1_AF2") (pintype "bidirectional"))
      (node (ref "U$2") (pin "BC2") (pinfunction "1_BC2") (pintype "bidirectional"))
      (node (ref "U$2") (pin "BF2") (pinfunction "1_BF2") (pintype "bidirectional"))
      (node (ref "U$2") (pin "CC2") (pinfunction "1_CC2") (pintype "bidirectional"))
      (node (ref "U$2") (pin "CF2") (pinfunction "1_CF2") (pintype "bidirectional"))
    )
    (net (code "43") (name "INITIALIZE") (class "Default")
      (node (ref "E28") (pin "4") (pinfunction "I0_4") (pintype "input"))
      (node (ref "Q1") (pin "1") (pinfunction "E_1") (pintype "passive"))
      (node (ref "U$2") (pin "CR1") (pinfunction "1_CR1") (pintype "bidirectional"))
    )
    (net (code "44") (name "KS_OK") (class "Default")
      (node (ref "E19") (pin "6") (pinfunction "O_6") (pintype "output"))
      (node (ref "E23") (pin "13") (pinfunction "I3_13") (pintype "input"))
      (node (ref "E23") (pin "5") (pinfunction "I3_5") (pintype "input"))
      (node (ref "E24") (pin "13") (pinfunction "I3_13") (pintype "input"))
      (node (ref "E24") (pin "5") (pinfunction "I3_5") (pintype "input"))
    )
    (net (code "45") (name "LA") (class "Default")
      (node (ref "E14") (pin "1") (pinfunction "~{Q1}_1") (pintype "output"))
      (node (ref "E23") (pin "1") (pinfunction "I0_1") (pintype "input"))
      (node (ref "E23") (pin "2") (pinfunction "I1_2") (pintype "input"))
    )
    (net (code "46") (name "LA+DEP") (class "Default")
      (node (ref "E31") (pin "9") (pinfunction "I1_9") (pintype "input"))
      (node (ref "E32") (pin "10") (pinfunction "I1_10") (pintype "input"))
      (node (ref "E33") (pin "6") (pinfunction "O_6") (pintype "output"))
    )
    (net (code "47") (name "LA+DEP+CONT") (class "Default")
      (node (ref "E26") (pin "1") (pinfunction "I0_1") (pintype "input"))
      (node (ref "E32") (pin "4") (pinfunction "I2_4") (pintype "input"))
      (node (ref "E32") (pin "5") (pinfunction "I3_5") (pintype "input"))
      (node (ref "E34") (pin "6") (pinfunction "O_6") (pintype "output"))
    )
    (net (code "48") (name "Net-(0-P)") (class "Default")
      (node (ref "0") (pin "1") (pinfunction "P_1") (pintype "passive"))
      (node (ref "E19") (pin "11") (pinfunction "O_11") (pintype "output"))
    )
    (net (code "49") (name "Net-(1-P)") (class "Default")
      (node (ref "1") (pin "1") (pinfunction "P_1") (pintype "passive"))
      (node (ref "E18") (pin "8") (pinfunction "O_8") (pintype "output"))
      (node (ref "E19") (pin "12") (pinfunction "I0_12") (pintype "input"))
      (node (ref "E19") (pin "13") (pinfunction "I1_13") (pintype "input"))
    )
    (net (code "50") (name "Net-(C5-Pad1)") (class "Default")
      (node (ref "C5") (pin "1") (pinfunction "1_1") (pintype "passive"))
      (node (ref "D5") (pin "C") (pinfunction "C_C") (pintype "passive"))
      (node (ref "R12") (pin "2") (pinfunction "2_2") (pintype "passive"))
      (node (ref "R14") (pin "1") (pinfunction "1_1") (pintype "passive"))
    )
    (net (code "51") (name "Net-(D3-PadA)") (class "Default")
      (node (ref "D3") (pin "A") (pinfunction "A_A") (pintype "passive"))
      (node (ref "R27") (pin "2") (pinfunction "2_2") (pintype "passive"))
    )
    (net (code "52") (name "Net-(E1B-I0)") (class "Default")
      (node (ref "E1") (pin "10") (pinfunction "I1_10") (pintype "input"))
      (node (ref "E1") (pin "9") (pinfunction "I0_9") (pintype "input"))
      (node (ref "E3") (pin "5") (pinfunction "Q_5") (pintype "output"))
      (node (ref "E8") (pin "9") (pinfunction "I_9") (pintype "input"))
    )
    (net (code "53") (name "Net-(E1B-I2)") (class "Default")
      (node (ref "C40") (pin "1") (pinfunction "1_1") (pintype "passive"))
      (node (ref "E1") (pin "12") (pinfunction "I2_12") (pintype "input"))
      (node (ref "E1") (pin "13") (pinfunction "I3_13") (pintype "input"))
      (node (ref "R11") (pin "2") (pinfunction "2_2") (pintype "passive"))
    )
    (net (code "54") (name "Net-(E1B-O)") (class "Default")
      (node (ref "E1") (pin "8") (pinfunction "O_8") (pintype "output"))
      (node (ref "E3") (pin "10") (pinfunction "PRE_10") (pintype "input"))
    )
    (net (code "55") (name "Net-(E2B-O)") (class "Default")
      (node (ref "E2") (pin "10") (pinfunction "I1_10") (pintype "input"))
      (node (ref "E2") (pin "6") (pinfunction "O_6") (pintype "output"))
      (node (ref "E2") (pin "9") (pinfunction "I0_9") (pintype "input"))
    )
    (net (code "56") (name "Net-(E2C-O)") (class "Default")
      (node (ref "E2") (pin "8") (pinfunction "O_8") (pintype "output"))
      (node (ref "E4") (pin "14") (pinfunction "CKA_14") (pintype "input"))
    )
    (net (code "57") (name "Net-(E3A-CLR)") (class "Default")
      (node (ref "E3") (pin "1") (pinfunction "CLR_1") (pintype "input"))
      (node (ref "R24") (pin "2") (pinfunction "2_2") (pintype "passive"))
      (node (ref "SET") (pin "1") (pinfunction "P_1") (pintype "passive"))
    )
    (net (code "58") (name "Net-(E3A-PRE)") (class "Default")
      (node (ref "E3") (pin "4") (pinfunction "PRE_4") (pintype "input"))
      (node (ref "R22") (pin "2") (pinfunction "2_2") (pintype "passive"))
      (node (ref "RES") (pin "1") (pinfunction "P_1") (pintype "passive"))
    )
    (net (code "59") (name "Net-(E8D-O)") (class "Default")
      (node (ref "E8") (pin "8") (pinfunction "O_8") (pintype "output"))
      (node (ref "R11") (pin "1") (pinfunction "1_1") (pintype "passive"))
    )
    (net (code "60") (name "Net-(E10A-I0)") (class "Default")
      (node (ref "E10") (pin "2") (pinfunction "I0_2") (pintype "input"))
      (node (ref "E10") (pin "3") (pinfunction "I1_3") (pintype "input"))
      (node (ref "E9") (pin "6") (pinfunction "O_6") (pintype "output"))
    )
    (net (code "61") (name "Net-(E10B-I0)") (class "Default")
      (node (ref "E10") (pin "5") (pinfunction "I0_5") (pintype "input"))
      (node (ref "E10") (pin "6") (pinfunction "I1_6") (pintype "input"))
      (node (ref "E9") (pin "8") (pinfunction "O_8") (pintype "output"))
    )
    (net (code "62") (name "Net-(E10C-I0)") (class "Default")
      (node (ref "D3") (pin "C") (pinfunction "C_C") (pintype "passive"))
      (node (ref "E1") (pin "6") (pinfunction "O_6") (pintype "output"))
      (node (ref "E10") (pin "8") (pinfunction "I0_8") (pintype "input"))
      (node (ref "E2") (pin "1") (pinfunction "I0_1") (pintype "input"))
      (node (ref "E2") (pin "2") (pinfunction "I1_2") (pintype "input"))
      (node (ref "R26") (pin "2") (pinfunction "2_2") (pintype "passive"))
    )
    (net (code "63") (name "Net-(E10C-O)") (class "Default")
      (node (ref "C39") (pin "1") (pinfunction "1_1") (pintype "passive"))
      (node (ref "D4") (pin "C") (pinfunction "C_C") (pintype "passive"))
      (node (ref "E1") (pin "1") (pinfunction "I0_1") (pintype "input"))
      (node (ref "E1") (pin "2") (pinfunction "I1_2") (pintype "input"))
      (node (ref "E1") (pin "4") (pinfunction "I2_4") (pintype "input"))
      (node (ref "E1") (pin "5") (pinfunction "I3_5") (pintype "input"))
      (node (ref "E10") (pin "10") (pinfunction "O_10") (pintype "open_collector"))
      (node (ref "R26") (pin "1") (pinfunction "1_1") (pintype "passive"))
      (node (ref "R27") (pin "1") (pinfunction "1_1") (pintype "passive"))
    )
    (net (code "64") (name "Net-(E15A-I1)") (class "Default")
      (node (ref "E15") (pin "12") (pinfunction "I1_12") (pintype "input"))
      (node (ref "E15") (pin "3") (pinfunction "I1_3") (pintype "input"))
      (node (ref "E15") (pin "6") (pinfunction "I1_6") (pintype "input"))
      (node (ref "E15") (pin "9") (pinfunction "I1_9") (pintype "input"))
      (node (ref "E16") (pin "12") (pinfunction "I1_12") (pintype "input"))
      (node (ref "E16") (pin "3") (pinfunction "I1_3") (pintype "input"))
      (node (ref "E16") (pin "6") (pinfunction "I1_6") (pintype "input"))
      (node (ref "E16") (pin "9") (pinfunction "I1_9") (pintype "input"))
      (node (ref "E17") (pin "11") (pinfunction "I0_11") (pintype "input"))
      (node (ref "E17") (pin "3") (pinfunction "I1_3") (pintype "input"))
      (node (ref "E17") (pin "6") (pinfunction "I1_6") (pintype "input"))
      (node (ref "E17") (pin "9") (pinfunction "I1_9") (pintype "input"))
      (node (ref "E8") (pin "10") (pinfunction "O_10") (pintype "output"))
      (node (ref "E8") (pin "12") (pinfunction "O_12") (pintype "output"))
    )
    (net (code "65") (name "Net-(E18A-I0)") (class "Default")
      (node (ref "C33") (pin "1") (pinfunction "1_1") (pintype "passive"))
      (node (ref "E18") (pin "1") (pinfunction "I0_1") (pintype "input"))
      (node (ref "E18") (pin "2") (pinfunction "I1_2") (pintype "input"))
      (node (ref "E18") (pin "4") (pinfunction "I2_4") (pintype "input"))
      (node (ref "E18") (pin "5") (pinfunction "I3_5") (pintype "input"))
      (node (ref "R4") (pin "2") (pinfunction "2_2") (pintype "passive"))
    )
    (net (code "66") (name "Net-(E18A-O)") (class "Default")
      (node (ref "C25") (pin "2") (pinfunction "2_2") (pintype "passive"))
      (node (ref "E18") (pin "6") (pinfunction "O_6") (pintype "output"))
    )
    (net (code "67") (name "Net-(E18B-I0)") (class "Default")
      (node (ref "D2") (pin "C") (pinfunction "C_C") (pintype "passive"))
      (node (ref "E18") (pin "10") (pinfunction "I1_10") (pintype "input"))
      (node (ref "E18") (pin "12") (pinfunction "I2_12") (pintype "input"))
      (node (ref "E18") (pin "13") (pinfunction "I3_13") (pintype "input"))
      (node (ref "E18") (pin "9") (pinfunction "I0_9") (pintype "input"))
      (node (ref "Q2") (pin "1") (pinfunction "E_1") (pintype "passive"))
      (node (ref "R1") (pin "2") (pinfunction "2_2") (pintype "passive"))
    )
    (net (code "68") (name "Net-(E19A-I1)") (class "Default")
      (node (ref "E19") (pin "2") (pinfunction "I1_2") (pintype "input"))
      (node (ref "E25") (pin "2") (pinfunction "O_2") (pintype "output"))
    )
    (net (code "69") (name "Net-(E19A-O)") (class "Default")
      (node (ref "E19") (pin "3") (pinfunction "O_3") (pintype "output"))
      (node (ref "E19") (pin "4") (pinfunction "I0_4") (pintype "input"))
    )
    (net (code "70") (name "Net-(E20A-C)") (class "Default")
      (node (ref "C44") (pin "2") (pinfunction "2_2") (pintype "passive"))
      (node (ref "E20") (pin "11") (pinfunction "C_11") (pintype "input"))
    )
    (net (code "71") (name "Net-(E20A-Q)") (class "Default")
      (node (ref "E20") (pin "8") (pinfunction "Q_8") (pintype "output"))
      (node (ref "E21") (pin "1") (pinfunction "A1_1") (pintype "input"))
      (node (ref "E21") (pin "2") (pinfunction "A2_2") (pintype "input"))
    )
    (net (code "72") (name "Net-(E20A-R{slash}C)") (class "Default")
      (node (ref "C44") (pin "1") (pinfunction "1_1") (pintype "passive"))
      (node (ref "E20") (pin "13") (pinfunction "R/C_13") (pintype "input"))
      (node (ref "R21") (pin "2") (pinfunction "2_2") (pintype "passive"))
    )
    (net (code "73") (name "Net-(E21A-B1)") (class "Default")
      (node (ref "C43") (pin "1") (pinfunction "1_1") (pintype "passive"))
      (node (ref "E21") (pin "3") (pinfunction "B1_3") (pintype "input"))
      (node (ref "E21") (pin "4") (pinfunction "B2_4") (pintype "input"))
      (node (ref "R19") (pin "1") (pinfunction "1_1") (pintype "passive"))
      (node (ref "R23") (pin "2") (pinfunction "2_2") (pintype "passive"))
    )
    (net (code "74") (name "Net-(E21A-C)") (class "Default")
      (node (ref "C42") (pin "2") (pinfunction "2_2") (pintype "passive"))
      (node (ref "E21") (pin "11") (pinfunction "C_11") (pintype "input"))
    )
    (net (code "75") (name "Net-(E21A-R{slash}C)") (class "Default")
      (node (ref "C42") (pin "1") (pinfunction "1_1") (pintype "passive"))
      (node (ref "E21") (pin "13") (pinfunction "R/C_13") (pintype "input"))
      (node (ref "R25") (pin "2") (pinfunction "2_2") (pintype "passive"))
    )
    (net (code "76") (name "Net-(E22A-B1)") (class "Default")
      (node (ref "E22") (pin "3") (pinfunction "B1_3") (pintype "input"))
      (node (ref "E22") (pin "4") (pinfunction "B2_4") (pintype "input"))
      (node (ref "E24") (pin "6") (pinfunction "O_6") (pintype "output"))
    )
    (net (code "77") (name "Net-(E22A-C)") (class "Default")
      (node (ref "C41") (pin "2") (pinfunction "2_2") (pintype "passive"))
      (node (ref "E22") (pin "11") (pinfunction "C_11") (pintype "input"))
    )
    (net (code "78") (name "Net-(E22A-R{slash}C)") (class "Default")
      (node (ref "C41") (pin "1") (pinfunction "1_1") (pintype "passive"))
      (node (ref "E22") (pin "13") (pinfunction "R/C_13") (pintype "input"))
      (node (ref "R17") (pin "2") (pinfunction "2_2") (pintype "passive"))
    )
    (net (code "79") (name "Net-(E25A-O)") (class "Default")
      (node (ref "E25") (pin "3") (pinfunction "O_3") (pintype "output"))
      (node (ref "R3") (pin "2") (pinfunction "2_2") (pintype "passive"))
    )
    (net (code "80") (name "Net-(E25B-I0)") (class "Default")
      (node (ref "E25") (pin "6") (pinfunction "I0_6") (pintype "input"))
      (node (ref "E25") (pin "7") (pinfunction "I1_7") (pintype "input"))
      (node (ref "KS") (pin "1") (pinfunction "P_1") (pintype "passive"))
    )
    (net (code "81") (name "Net-(E25C-O)") (class "Default")
      (node (ref "E25") (pin "14") (pinfunction "O_14") (pintype "output"))
      (node (ref "H") (pin "1") (pinfunction "P_1") (pintype "passive"))
    )
    (net (code "82") (name "Net-(E26A-O)") (class "Default")
      (node (ref "E26") (pin "3") (pinfunction "O_3") (pintype "output"))
      (node (ref "E26") (pin "4") (pinfunction "I0_4") (pintype "input"))
      (node (ref "E26") (pin "5") (pinfunction "I1_5") (pintype "input"))
    )
    (net (code "83") (name "Net-(E26B-O)") (class "Default")
      (node (ref "E26") (pin "12") (pinfunction "I0_12") (pintype "input"))
      (node (ref "E26") (pin "6") (pinfunction "O_6") (pintype "output"))
    )
    (net (code "84") (name "Net-(E26C-I0)") (class "Default")
      (node (ref "E26") (pin "13") (pinfunction "I1_13") (pintype "input"))
      (node (ref "E26") (pin "9") (pinfunction "I0_9") (pintype "input"))
      (node (ref "E34") (pin "8") (pinfunction "O_8") (pintype "output"))
    )
    (net (code "85") (name "Net-(E26C-I1)") (class "Default")
      (node (ref "E26") (pin "10") (pinfunction "I1_10") (pintype "input"))
      (node (ref "E26") (pin "11") (pinfunction "O_11") (pintype "output"))
    )
    (net (code "86") (name "Net-(E27A-O)") (class "Default")
      (node (ref "E27") (pin "3") (pinfunction "O_3") (pintype "output"))
      (node (ref "R15") (pin "2") (pinfunction "2_2") (pintype "passive"))
    )
    (net (code "87") (name "Net-(E28A-O)") (class "Default")
      (node (ref "E28") (pin "3") (pinfunction "O_3") (pintype "output"))
      (node (ref "E34") (pin "12") (pinfunction "I2_12") (pintype "input"))
      (node (ref "E34") (pin "13") (pinfunction "I3_13") (pintype "input"))
    )
    (net (code "88") (name "Net-(E28B-O)") (class "Default")
      (node (ref "E28") (pin "2") (pinfunction "O_2") (pintype "output"))
      (node (ref "E34") (pin "10") (pinfunction "I1_10") (pintype "input"))
    )
    (net (code "89") (name "Net-(E28C-I0)") (class "Default")
      (node (ref "C25") (pin "1") (pinfunction "1_1") (pintype "passive"))
      (node (ref "E28") (pin "9") (pinfunction "I0_9") (pintype "input"))
      (node (ref "R13") (pin "1") (pinfunction "1_1") (pintype "passive"))
    )
    (net (code "90") (name "Net-(E28C-O)") (class "Default")
      (node (ref "C45") (pin "2") (pinfunction "2_2") (pintype "passive"))
      (node (ref "E28") (pin "14") (pinfunction "O_14") (pintype "output"))
    )
    (net (code "91") (name "Net-(E28D-I1)") (class "Default")
      (node (ref "C45") (pin "1") (pinfunction "1_1") (pintype "passive"))
      (node (ref "D5") (pin "A") (pinfunction "A_A") (pintype "passive"))
      (node (ref "E28") (pin "12") (pinfunction "I1_12") (pintype "input"))
      (node (ref "R16") (pin "2") (pinfunction "2_2") (pintype "passive"))
    )
    (net (code "92") (name "Net-(E29B-O)") (class "Default")
      (node (ref "E29") (pin "6") (pinfunction "O_6") (pintype "output"))
      (node (ref "E30") (pin "8") (pinfunction "I0_8") (pintype "input"))
      (node (ref "E30") (pin "9") (pinfunction "I1_9") (pintype "input"))
    )
    (net (code "93") (name "Net-(E29D-O)") (class "Default")
      (node (ref "E29") (pin "11") (pinfunction "O_11") (pintype "output"))
      (node (ref "E30") (pin "2") (pinfunction "I0_2") (pintype "input"))
      (node (ref "E30") (pin "3") (pinfunction "I1_3") (pintype "input"))
    )
    (net (code "94") (name "Net-(E30A-O)") (class "Default")
      (node (ref "E30") (pin "1") (pinfunction "O_1") (pintype "open_collector"))
      (node (ref "R28") (pin "2") (pinfunction "2_2") (pintype "passive"))
      (node (ref "R6") (pin "2") (pinfunction "2_2") (pintype "passive"))
    )
    (net (code "95") (name "Net-(E30C-O)") (class "Default")
      (node (ref "E30") (pin "10") (pinfunction "O_10") (pintype "open_collector"))
      (node (ref "R8") (pin "1") (pinfunction "1_1") (pintype "passive"))
      (node (ref "R9") (pin "1") (pinfunction "1_1") (pintype "passive"))
    )
    (net (code "96") (name "Net-(E32A-I0)") (class "Default")
      (node (ref "C4") (pin "1") (pinfunction "1_1") (pintype "passive"))
      (node (ref "E32") (pin "1") (pinfunction "I0_1") (pintype "input"))
      (node (ref "E32") (pin "2") (pinfunction "I1_2") (pintype "input"))
      (node (ref "R15") (pin "1") (pinfunction "1_1") (pintype "passive"))
    )
    (net (code "97") (name "Net-(E32A-O)") (class "Default")
      (node (ref "E32") (pin "6") (pinfunction "O_6") (pintype "output"))
      (node (ref "R4") (pin "1") (pinfunction "1_1") (pintype "passive"))
    )
    (net (code "98") (name "Net-(E32B-O)") (class "Default")
      (node (ref "E32") (pin "8") (pinfunction "O_8") (pintype "output"))
      (node (ref "E8") (pin "11") (pinfunction "I_11") (pintype "input"))
      (node (ref "E8") (pin "13") (pinfunction "I_13") (pintype "input"))
    )
    (net (code "99") (name "Net-(Q1-B)") (class "Default")
      (node (ref "Q1") (pin "2") (pinfunction "B_2") (pintype "passive"))
      (node (ref "R8") (pin "2") (pinfunction "2_2") (pintype "passive"))
    )
    (net (code "100") (name "Net-(Q1-C)") (class "Default")
      (node (ref "Q1") (pin "3") (pinfunction "C_3") (pintype "passive"))
      (node (ref "R10") (pin "1") (pinfunction "1_1") (pintype "passive"))
    )
    (net (code "101") (name "Net-(Q2-B)") (class "Default")
      (node (ref "C7") (pin "+") (pinfunction "+_+") (pintype "passive"))
      (node (ref "Q2") (pin "2") (pinfunction "B_2") (pintype "passive"))
      (node (ref "R3") (pin "1") (pinfunction "1_1") (pintype "passive"))
    )
    (net (code "102") (name "Net-(Q2-C)") (class "Default")
      (node (ref "Q2") (pin "3") (pinfunction "C_3") (pintype "passive"))
      (node (ref "R2") (pin "1") (pinfunction "1_1") (pintype "passive"))
    )
    (net (code "103") (name "Net-(Q3-B)") (class "Default")
      (node (ref "Q3") (pin "2") (pinfunction "B_2") (pintype "passive"))
      (node (ref "R6") (pin "1") (pinfunction "1_1") (pintype "passive"))
    )
    (net (code "104") (name "Net-(Q3-C)") (class "Default")
      (node (ref "Q3") (pin "3") (pinfunction "C_3") (pintype "passive"))
      (node (ref "R5") (pin "2") (pinfunction "2_2") (pintype "passive"))
    )
    (net (code "105") (name "Net-(U$2AU-1)") (class "Default")
      (node (ref "U$2") (pin "BF1") (pinfunction "1_BF1") (pintype "bidirectional"))
      (node (ref "U$2") (pin "BN1") (pinfunction "1_BN1") (pintype "bidirectional"))
    )
    (net (code "106") (name "Net-(U$2CZ-1)") (class "Default")
      (node (ref "U$2") (pin "CT2") (pinfunction "1_CT2") (pintype "bidirectional"))
      (node (ref "U$2") (pin "DF2") (pinfunction "1_DF2") (pintype "bidirectional"))
      (node (ref "U$2") (pin "DN2") (pinfunction "1_DN2") (pintype "bidirectional"))
    )
    (net (code "107") (name "Net-(U$2D-1)") (class "Default")
      (node (ref "R7") (pin "1") (pinfunction "1_1") (pintype "passive"))
      (node (ref "U$2") (pin "AB2") (pinfunction "1_AB2") (pintype "bidirectional"))
    )
    (net (code "108") (name "Net-(U$2DO-1)") (class "Default")
      (node (ref "U$2") (pin "DF1") (pinfunction "1_DF1") (pintype "bidirectional"))
      (node (ref "U$2") (pin "DN1") (pinfunction "1_DN1") (pintype "bidirectional"))
    )
    (net (code "109") (name "Net-(U$2K-1)") (class "Default")
      (node (ref "U$2") (pin "AF1") (pinfunction "1_AF1") (pintype "bidirectional"))
      (node (ref "U$2") (pin "AN1") (pinfunction "1_AN1") (pintype "bidirectional"))
    )
    (net (code "110") (name "ODD") (class "Default")
      (node (ref "E10") (pin "1") (pinfunction "O_1") (pintype "open_collector"))
      (node (ref "E13") (pin "13") (pinfunction "C12_13") (pintype "input"))
      (node (ref "E13") (pin "4") (pinfunction "C34_4") (pintype "input"))
      (node (ref "E14") (pin "13") (pinfunction "C12_13") (pintype "input"))
      (node (ref "E14") (pin "4") (pinfunction "C34_4") (pintype "input"))
      (node (ref "E20") (pin "3") (pinfunction "B1_3") (pintype "input"))
      (node (ref "E20") (pin "4") (pinfunction "B2_4") (pintype "input"))
      (node (ref "R20") (pin "2") (pinfunction "2_2") (pintype "passive"))
    )
    (net (code "111") (name "PULSE") (class "Default")
      (node (ref "E28") (pin "10") (pinfunction "I1_10") (pintype "input"))
      (node (ref "E28") (pin "13") (pinfunction "O_13") (pintype "output"))
      (node (ref "E29") (pin "13") (pinfunction "I1_13") (pintype "input"))
      (node (ref "E29") (pin "5") (pinfunction "I1_5") (pintype "input"))
      (node (ref "E30") (pin "5") (pinfunction "I0_5") (pintype "input"))
    )
    (net (code "112") (name "PULSE_LA") (class "Default")
      (node (ref "Q3") (pin "1") (pinfunction "E_1") (pintype "passive"))
      (node (ref "U$2") (pin "DR2") (pinfunction "1_DR2") (pintype "bidirectional"))
    )
    (net (code "113") (name "SWITCH") (class "Default")
      (node (ref "E25") (pin "4") (pinfunction "I0_4") (pintype "input"))
      (node (ref "E25") (pin "5") (pinfunction "I1_5") (pintype "input"))
      (node (ref "N") (pin "1") (pinfunction "P_1") (pintype "passive"))
      (node (ref "U$2") (pin "DV2") (pinfunction "1_DV2") (pintype "bidirectional"))
    )
    (net (code "114") (name "TIMER1") (class "Default")
      (node (ref "E19") (pin "8") (pinfunction "O_8") (pintype "output"))
      (node (ref "E24") (pin "10") (pinfunction "I1_10") (pintype "input"))
      (node (ref "E24") (pin "9") (pinfunction "I0_9") (pintype "input"))
    )
    (net (code "115") (name "TIMER2") (class "Default")
      (node (ref "E21") (pin "8") (pinfunction "Q_8") (pintype "output"))
      (node (ref "E23") (pin "12") (pinfunction "I2_12") (pintype "input"))
      (node (ref "E23") (pin "4") (pinfunction "I2_4") (pintype "input"))
      (node (ref "E24") (pin "4") (pinfunction "I2_4") (pintype "input"))
    )
    (net (code "116") (name "TP4") (class "Default")
      (node (ref "E28") (pin "6") (pinfunction "I0_6") (pintype "input"))
      (node (ref "U$2") (pin "CJ2") (pinfunction "1_CJ2") (pintype "bidirectional"))
    )
    (net (code "117") (name "TS4L") (class "Default")
      (node (ref "E27") (pin "13") (pinfunction "O_13") (pintype "output"))
      (node (ref "E32") (pin "12") (pinfunction "I2_12") (pintype "input"))
      (node (ref "E32") (pin "13") (pinfunction "I3_13") (pintype "input"))
    )
    (net (code "118") (name "VCC") (class "Default")
      (node (ref "C1") (pin "1") (pinfunction "1_1") (pintype "passive"))
      (node (ref "C11") (pin "1") (pinfunction "1_1") (pintype "passive"))
      (node (ref "C12") (pin "1") (pinfunction "1_1") (pintype "passive"))
      (node (ref "C15") (pin "1") (pinfunction "1_1") (pintype "passive"))
      (node (ref "C16") (pin "1") (pinfunction "1_1") (pintype "passive"))
      (node (ref "C18") (pin "1") (pinfunction "1_1") (pintype "passive"))
      (node (ref "C2") (pin "1") (pinfunction "1_1") (pintype "passive"))
      (node (ref "C21") (pin "1") (pinfunction "1_1") (pintype "passive"))
      (node (ref "C24") (pin "1") (pinfunction "1_1") (pintype "passive"))
      (node (ref "C28") (pin "1") (pinfunction "1_1") (pintype "passive"))
      (node (ref "C29") (pin "1") (pinfunction "1_1") (pintype "passive"))
      (node (ref "C3") (pin "1") (pinfunction "1_1") (pintype "passive"))
      (node (ref "C31") (pin "1") (pinfunction "1_1") (pintype "passive"))
      (node (ref "C32") (pin "1") (pinfunction "1_1") (pintype "passive"))
      (node (ref "C34") (pin "+") (pinfunction "+_+") (pintype "passive"))
      (node (ref "C35") (pin "+") (pinfunction "+_+") (pintype "passive"))
      (node (ref "C36") (pin "+") (pinfunction "+_+") (pintype "passive"))
      (node (ref "C6") (pin "1") (pinfunction "1_1") (pintype "passive"))
      (node (ref "E6") (pin "12") (pinfunction "VCC1_12") (pintype "input"))
      (node (ref "E6") (pin "13") (pinfunction "P_13") (pintype "input"))
      (node (ref "E6") (pin "15") (pinfunction "VBB_15") (pintype "input"))
      (node (ref "E6") (pin "22") (pinfunction "VCC2_22") (pintype "input"))
      (node (ref "E6") (pin "23") (pinfunction "VCC3_23") (pintype "input"))
      (node (ref "R10") (pin "2") (pinfunction "2_2") (pintype "passive"))
      (node (ref "R12") (pin "1") (pinfunction "1_1") (pintype "passive"))
      (node (ref "R16") (pin "1") (pinfunction "1_1") (pintype "passive"))
      (node (ref "R17") (pin "1") (pinfunction "1_1") (pintype "passive"))
      (node (ref "R18") (pin "1") (pinfunction "1_1") (pintype "passive"))
      (node (ref "R2") (pin "2") (pinfunction "2_2") (pintype "passive"))
      (node (ref "R20") (pin "1") (pinfunction "1_1") (pintype "passive"))
      (node (ref "R21") (pin "1") (pinfunction "1_1") (pintype "passive"))
      (node (ref "R22") (pin "1") (pinfunction "1_1") (pintype "passive"))
      (node (ref "R23") (pin "1") (pinfunction "1_1") (pintype "passive"))
      (node (ref "R24") (pin "1") (pinfunction "1_1") (pintype "passive"))
      (node (ref "R25") (pin "1") (pinfunction "1_1") (pintype "passive"))
      (node (ref "R28") (pin "1") (pinfunction "1_1") (pintype "passive"))
      (node (ref "R5") (pin "1") (pinfunction "1_1") (pintype "passive"))
      (node (ref "R9") (pin "2") (pinfunction "2_2") (pintype "passive"))
      (node (ref "U$2") (pin "AA2") (pinfunction "1_AA2") (pintype "bidirectional"))
      (node (ref "U$2") (pin "BA2") (pinfunction "1_BA2") (pintype "bidirectional"))
      (node (ref "U$2") (pin "CA2") (pinfunction "1_CA2") (pintype "bidirectional"))
    )
    (net (code "119") (name "VDD") (class "Default")
      (node (ref "C19") (pin "2") (pinfunction "2_2") (pintype "passive"))
      (node (ref "C37") (pin "-") (pinfunction "-_-") (pintype "passive"))
      (node (ref "D1") (pin "A") (pinfunction "A_A") (pintype "passive"))
      (node (ref "E6") (pin "16") (pinfunction "VGG_16") (pintype "input"))
      (node (ref "E6") (pin "24") (pinfunction "VDD_24") (pintype "input"))
      (node (ref "R7") (pin "2") (pinfunction "2_2") (pintype "passive"))
    )
    (net (code "120") (name "unconnected-(E3A-~{Q}-Pad6)") (class "Default")
      (node (ref "E3") (pin "6") (pinfunction "~{Q}_6") (pintype "output"))
    )
    (net (code "121") (name "unconnected-(E11A-Q1-Pad16)") (class "Default")
      (node (ref "E11") (pin "16") (pinfunction "Q1_16") (pintype "output"))
    )
    (net (code "122") (name "unconnected-(E11A-Q2-Pad15)") (class "Default")
      (node (ref "E11") (pin "15") (pinfunction "Q2_15") (pintype "output"))
    )
    (net (code "123") (name "unconnected-(E11A-Q3-Pad10)") (class "Default")
      (node (ref "E11") (pin "10") (pinfunction "Q3_10") (pintype "output"))
    )
    (net (code "124") (name "unconnected-(E11A-Q4-Pad9)") (class "Default")
      (node (ref "E11") (pin "9") (pinfunction "Q4_9") (pintype "output"))
    )
    (net (code "125") (name "unconnected-(E12A-Q1-Pad16)") (class "Default")
      (node (ref "E12") (pin "16") (pinfunction "Q1_16") (pintype "output"))
    )
    (net (code "126") (name "unconnected-(E12A-Q2-Pad15)") (class "Default")
      (node (ref "E12") (pin "15") (pinfunction "Q2_15") (pintype "output"))
    )
    (net (code "127") (name "unconnected-(E12A-Q3-Pad10)") (class "Default")
      (node (ref "E12") (pin "10") (pinfunction "Q3_10") (pintype "output"))
    )
    (net (code "128") (name "unconnected-(E12A-Q4-Pad9)") (class "Default")
      (node (ref "E12") (pin "9") (pinfunction "Q4_9") (pintype "output"))
    )
    (net (code "129") (name "unconnected-(E13A-Q1-Pad16)") (class "Default")
      (node (ref "E13") (pin "16") (pinfunction "Q1_16") (pintype "output"))
    )
    (net (code "130") (name "unconnected-(E13A-Q2-Pad15)") (class "Default")
      (node (ref "E13") (pin "15") (pinfunction "Q2_15") (pintype "output"))
    )
    (net (code "131") (name "unconnected-(E13A-Q3-Pad10)") (class "Default")
      (node (ref "E13") (pin "10") (pinfunction "Q3_10") (pintype "output"))
    )
    (net (code "132") (name "unconnected-(E13A-Q4-Pad9)") (class "Default")
      (node (ref "E13") (pin "9") (pinfunction "Q4_9") (pintype "output"))
    )
    (net (code "133") (name "unconnected-(E14A-Q1-Pad16)") (class "Default")
      (node (ref "E14") (pin "16") (pinfunction "Q1_16") (pintype "output"))
    )
    (net (code "134") (name "unconnected-(E14A-Q2-Pad15)") (class "Default")
      (node (ref "E14") (pin "15") (pinfunction "Q2_15") (pintype "output"))
    )
    (net (code "135") (name "unconnected-(E14A-Q3-Pad10)") (class "Default")
      (node (ref "E14") (pin "10") (pinfunction "Q3_10") (pintype "output"))
    )
    (net (code "136") (name "unconnected-(E14A-Q4-Pad9)") (class "Default")
      (node (ref "E14") (pin "9") (pinfunction "Q4_9") (pintype "output"))
    )
    (net (code "137") (name "unconnected-(E20A-CLR-Pad5)") (class "Default")
      (node (ref "E20") (pin "5") (pinfunction "CLR_5") (pintype "input"))
    )
    (net (code "138") (name "unconnected-(E20A-R-Pad9)") (class "Default")
      (node (ref "E20") (pin "9") (pinfunction "R_9") (pintype "input"))
    )
    (net (code "139") (name "unconnected-(E21A-CLR-Pad5)") (class "Default")
      (node (ref "E21") (pin "5") (pinfunction "CLR_5") (pintype "input"))
    )
    (net (code "140") (name "unconnected-(E21A-R-Pad9)") (class "Default")
      (node (ref "E21") (pin "9") (pinfunction "R_9") (pintype "input"))
    )
    (net (code "141") (name "unconnected-(E21A-~{Q}-Pad6)") (class "Default")
      (node (ref "E21") (pin "6") (pinfunction "~{Q}_6") (pintype "output"))
    )
    (net (code "142") (name "unconnected-(E22A-CLR-Pad5)") (class "Default")
      (node (ref "E22") (pin "5") (pinfunction "CLR_5") (pintype "input"))
    )
    (net (code "143") (name "unconnected-(E22A-Q-Pad8)") (class "Default")
      (node (ref "E22") (pin "8") (pinfunction "Q_8") (pintype "output"))
    )
    (net (code "144") (name "unconnected-(E22A-R-Pad9)") (class "Default")
      (node (ref "E22") (pin "9") (pinfunction "R_9") (pintype "input"))
    )
    (net (code "145") (name "~{A0}") (class "Default")
      (node (ref "E8") (pin "6") (pinfunction "O_6") (pintype "output"))
      (node (ref "E9") (pin "12") (pinfunction "I2_12") (pintype "input"))
      (node (ref "E9") (pin "13") (pinfunction "I3_13") (pintype "input"))
    )
    (net (code "146") (name "~{ACTIVE}") (class "Default")
      (node (ref "E10") (pin "9") (pinfunction "I1_9") (pintype "input"))
      (node (ref "E3") (pin "8") (pinfunction "~{Q}_8") (pintype "output"))
      (node (ref "E4") (pin "2") (pinfunction "R0(1)_2") (pintype "input"))
      (node (ref "E4") (pin "3") (pinfunction "R0(2)_3") (pintype "input"))
      (node (ref "E5") (pin "2") (pinfunction "R0(1)_2") (pintype "input"))
      (node (ref "E5") (pin "3") (pinfunction "R0(2)_3") (pintype "input"))
    )
    (net (code "147") (name "~{BRK_DATA_CONT}") (class "Default")
      (node (ref "E30") (pin "13") (pinfunction "O_13") (pintype "open_collector"))
      (node (ref "U$2") (pin "BK2") (pinfunction "1_BK2") (pintype "bidirectional"))
    )
    (net (code "148") (name "~{BRUN}") (class "Default")
      (node (ref "E27") (pin "6") (pinfunction "I0_6") (pintype "input"))
      (node (ref "U$2") (pin "BU2") (pinfunction "1_BU2") (pintype "bidirectional"))
    )
    (net (code "149") (name "~{CS}") (class "Default")
      (node (ref "E2") (pin "11") (pinfunction "O_11") (pintype "output"))
      (node (ref "E6") (pin "14") (pinfunction "~{CS}_14") (pintype "input"))
    )
    (net (code "150") (name "~{D0}") (class "Default")
      (node (ref "E12") (pin "7") (pinfunction "D4_7") (pintype "input"))
      (node (ref "E14") (pin "7") (pinfunction "D4_7") (pintype "input"))
      (node (ref "E7") (pin "2") (pinfunction "O_2") (pintype "output"))
    )
    (net (code "151") (name "~{D1}") (class "Default")
      (node (ref "E12") (pin "6") (pinfunction "D3_6") (pintype "input"))
      (node (ref "E14") (pin "6") (pinfunction "D3_6") (pintype "input"))
      (node (ref "E7") (pin "4") (pinfunction "O_4") (pintype "output"))
    )
    (net (code "152") (name "~{D2}") (class "Default")
      (node (ref "E12") (pin "3") (pinfunction "D2_3") (pintype "input"))
      (node (ref "E14") (pin "3") (pinfunction "D2_3") (pintype "input"))
      (node (ref "E7") (pin "6") (pinfunction "O_6") (pintype "output"))
    )
    (net (code "153") (name "~{D3}") (class "Default")
      (node (ref "E12") (pin "2") (pinfunction "D1_2") (pintype "input"))
      (node (ref "E14") (pin "2") (pinfunction "D1_2") (pintype "input"))
      (node (ref "E7") (pin "8") (pinfunction "O_8") (pintype "output"))
    )
    (net (code "154") (name "~{D4}") (class "Default")
      (node (ref "E11") (pin "7") (pinfunction "D4_7") (pintype "input"))
      (node (ref "E13") (pin "7") (pinfunction "D4_7") (pintype "input"))
      (node (ref "E7") (pin "10") (pinfunction "O_10") (pintype "output"))
    )
    (net (code "155") (name "~{D5}") (class "Default")
      (node (ref "E11") (pin "6") (pinfunction "D3_6") (pintype "input"))
      (node (ref "E13") (pin "6") (pinfunction "D3_6") (pintype "input"))
      (node (ref "E7") (pin "12") (pinfunction "O_12") (pintype "output"))
    )
    (net (code "156") (name "~{D6}") (class "Default")
      (node (ref "E11") (pin "3") (pinfunction "D2_3") (pintype "input"))
      (node (ref "E13") (pin "3") (pinfunction "D2_3") (pintype "input"))
      (node (ref "E8") (pin "2") (pinfunction "O_2") (pintype "output"))
    )
    (net (code "157") (name "~{D7}") (class "Default")
      (node (ref "E11") (pin "2") (pinfunction "D1_2") (pintype "input"))
      (node (ref "E13") (pin "2") (pinfunction "D1_2") (pintype "input"))
      (node (ref "E8") (pin "4") (pinfunction "O_4") (pintype "output"))
    )
    (net (code "158") (name "~{DATA0}") (class "Default")
      (node (ref "E17") (pin "13") (pinfunction "O_13") (pintype "open_collector"))
      (node (ref "U$2") (pin "AR1") (pinfunction "1_AR1") (pintype "bidirectional"))
    )
    (net (code "159") (name "~{DATA1}") (class "Default")
      (node (ref "E17") (pin "10") (pinfunction "O_10") (pintype "open_collector"))
      (node (ref "U$2") (pin "AS1") (pinfunction "1_AS1") (pintype "bidirectional"))
    )
    (net (code "160") (name "~{DATA2}") (class "Default")
      (node (ref "E17") (pin "4") (pinfunction "O_4") (pintype "open_collector"))
      (node (ref "U$2") (pin "AU1") (pinfunction "1_AU1") (pintype "bidirectional"))
    )
    (net (code "161") (name "~{DATA3}") (class "Default")
      (node (ref "E17") (pin "1") (pinfunction "O_1") (pintype "open_collector"))
      (node (ref "U$2") (pin "AV1") (pinfunction "1_AV1") (pintype "bidirectional"))
    )
    (net (code "162") (name "~{DATA4}") (class "Default")
      (node (ref "E16") (pin "13") (pinfunction "O_13") (pintype "open_collector"))
      (node (ref "U$2") (pin "BR1") (pinfunction "1_BR1") (pintype "bidirectional"))
    )
    (net (code "163") (name "~{DATA5}") (class "Default")
      (node (ref "E16") (pin "10") (pinfunction "O_10") (pintype "open_collector"))
      (node (ref "U$2") (pin "BS1") (pinfunction "1_BS1") (pintype "bidirectional"))
    )
    (net (code "164") (name "~{DATA6}") (class "Default")
      (node (ref "E16") (pin "4") (pinfunction "O_4") (pintype "open_collector"))
      (node (ref "U$2") (pin "BU1") (pinfunction "1_BU1") (pintype "bidirectional"))
    )
    (net (code "165") (name "~{DATA7}") (class "Default")
      (node (ref "E16") (pin "1") (pinfunction "O_1") (pintype "open_collector"))
      (node (ref "U$2") (pin "BV1") (pinfunction "1_BV1") (pintype "bidirectional"))
    )
    (net (code "166") (name "~{DATA8}") (class "Default")
      (node (ref "E15") (pin "13") (pinfunction "O_13") (pintype "open_collector"))
      (node (ref "U$2") (pin "DR1") (pinfunction "1_DR1") (pintype "bidirectional"))
    )
    (net (code "167") (name "~{DATA9}") (class "Default")
      (node (ref "E15") (pin "10") (pinfunction "O_10") (pintype "open_collector"))
      (node (ref "U$2") (pin "DS1") (pinfunction "1_DS1") (pintype "bidirectional"))
    )
    (net (code "168") (name "~{DATA10}") (class "Default")
      (node (ref "E15") (pin "4") (pinfunction "O_4") (pintype "open_collector"))
      (node (ref "U$2") (pin "DU1") (pinfunction "1_DU1") (pintype "bidirectional"))
    )
    (net (code "169") (name "~{DATA11}") (class "Default")
      (node (ref "E15") (pin "1") (pinfunction "O_1") (pintype "open_collector"))
      (node (ref "U$2") (pin "DV1") (pinfunction "1_DV1") (pintype "bidirectional"))
    )
    (net (code "170") (name "~{DOCLR}") (class "Default")
      (node (ref "E24") (pin "8") (pinfunction "O_8") (pintype "output"))
      (node (ref "E29") (pin "1") (pinfunction "I0_1") (pintype "input"))
      (node (ref "E29") (pin "2") (pinfunction "I1_2") (pintype "input"))
      (node (ref "E34") (pin "5") (pinfunction "I3_5") (pintype "input"))
    )
    (net (code "171") (name "~{DODEP}") (class "Default")
      (node (ref "E23") (pin "8") (pinfunction "O_8") (pintype "output"))
      (node (ref "E29") (pin "9") (pinfunction "I0_9") (pintype "input"))
      (node (ref "E33") (pin "1") (pinfunction "I0_1") (pintype "input"))
      (node (ref "E33") (pin "2") (pinfunction "I1_2") (pintype "input"))
      (node (ref "E33") (pin "5") (pinfunction "I1_5") (pintype "input"))
      (node (ref "E34") (pin "2") (pinfunction "I1_2") (pintype "input"))
    )
    (net (code "172") (name "~{DOLA}") (class "Default")
      (node (ref "E23") (pin "6") (pinfunction "O_6") (pintype "output"))
      (node (ref "E33") (pin "10") (pinfunction "I1_10") (pintype "input"))
      (node (ref "E33") (pin "4") (pinfunction "I0_4") (pintype "input"))
      (node (ref "E33") (pin "9") (pinfunction "I0_9") (pintype "input"))
      (node (ref "E34") (pin "1") (pinfunction "I0_1") (pintype "input"))
    )
    (net (code "173") (name "~{KEY_CONT}") (class "Default")
      (node (ref "E31") (pin "4") (pinfunction "O_4") (pintype "open_collector"))
      (node (ref "U$2") (pin "DU2") (pinfunction "1_DU2") (pintype "bidirectional"))
    )
    (net (code "174") (name "~{LA_ENABLE}") (class "Default")
      (node (ref "E31") (pin "1") (pinfunction "O_1") (pintype "open_collector"))
      (node (ref "U$2") (pin "BM2") (pinfunction "1_BM2") (pintype "bidirectional"))
    )
    (net (code "175") (name "~{MD_DIR}") (class "Default")
      (node (ref "E31") (pin "13") (pinfunction "O_13") (pintype "open_collector"))
      (node (ref "U$2") (pin "AK2") (pinfunction "1_AK2") (pintype "bidirectional"))
    )
    (net (code "176") (name "~{MEM_START}") (class "Default")
      (node (ref "E30") (pin "4") (pinfunction "O_4") (pintype "open_collector"))
      (node (ref "U$2") (pin "AJ2") (pinfunction "1_AJ2") (pintype "bidirectional"))
    )
    (net (code "177") (name "~{MS_DISABLE}") (class "Default")
      (node (ref "E31") (pin "10") (pinfunction "O_10") (pintype "open_collector"))
      (node (ref "U$2") (pin "CV1") (pinfunction "1_CV1") (pintype "bidirectional"))
    )
    (net (code "178") (name "~{RUN}") (class "Default")
      (node (ref "E26") (pin "2") (pinfunction "I1_2") (pintype "input"))
      (node (ref "E27") (pin "2") (pinfunction "O_2") (pintype "output"))
      (node (ref "E27") (pin "4") (pinfunction "I0_4") (pintype "input"))
      (node (ref "E27") (pin "5") (pinfunction "I1_5") (pintype "input"))
    )
    (net (code "179") (name "~{STOP}") (class "Default")
      (node (ref "E10") (pin "13") (pinfunction "O_13") (pintype "open_collector"))
      (node (ref "U$2") (pin "DS2") (pinfunction "1_DS2") (pintype "bidirectional"))
    )
    (net (code "180") (name "~{TIMER1}") (class "Default")
      (node (ref "E19") (pin "10") (pinfunction "I1_10") (pintype "input"))
      (node (ref "E19") (pin "9") (pinfunction "I0_9") (pintype "input"))
      (node (ref "E20") (pin "6") (pinfunction "~{Q}_6") (pintype "output"))
    )
    (net (code "181") (name "~{TS4}") (class "Default")
      (node (ref "E27") (pin "11") (pinfunction "I0_11") (pintype "input"))
      (node (ref "U$2") (pin "CP2") (pinfunction "1_CP2") (pintype "bidirectional"))
    )
  )
)
